# KVR_LABS_-_AEV_ENCODER_1_01-STM32.net
KiCad netlist of a schematic drawn in EAGLE
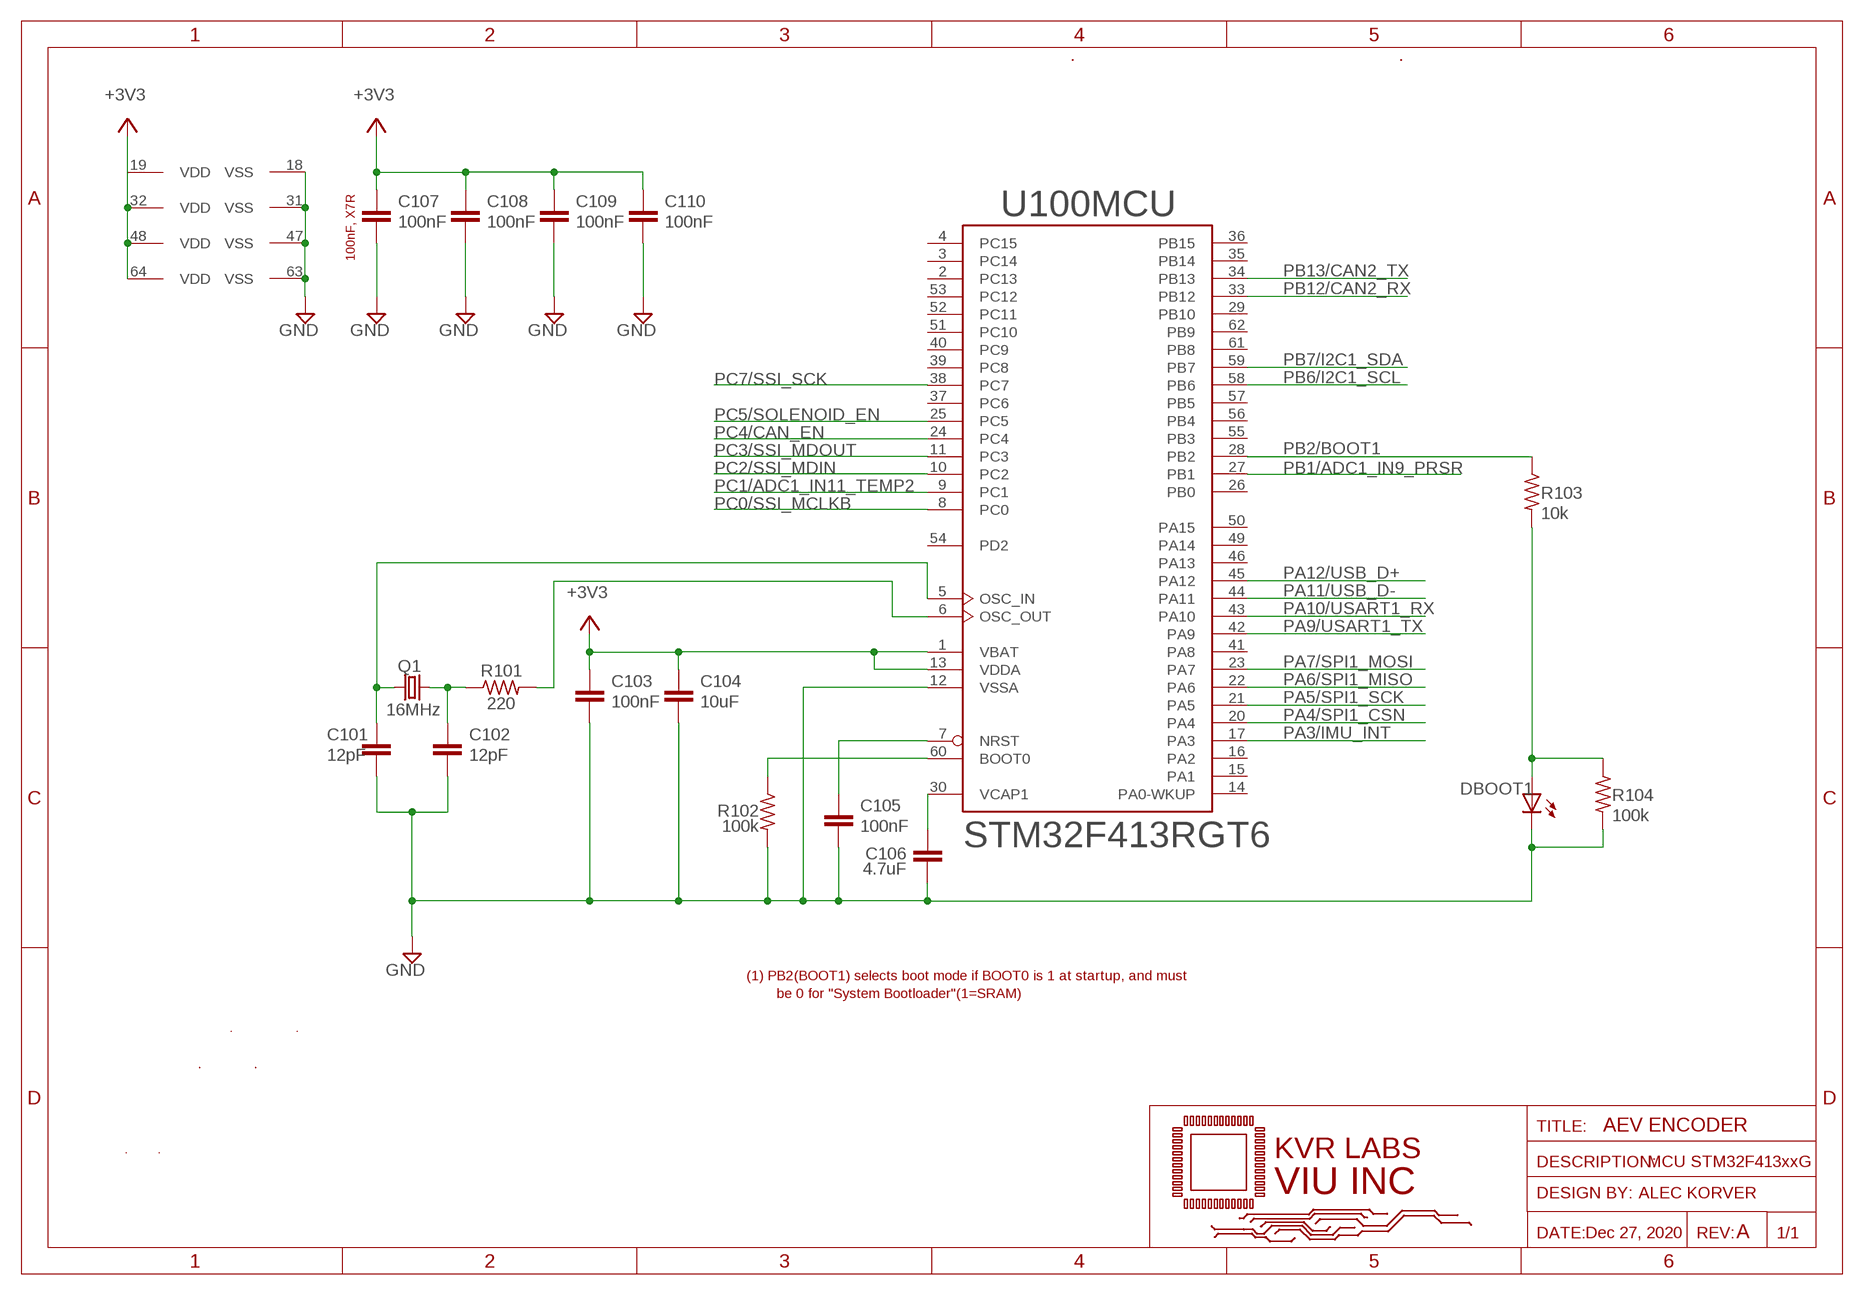
[diagram p0: schematic, sheet 1]
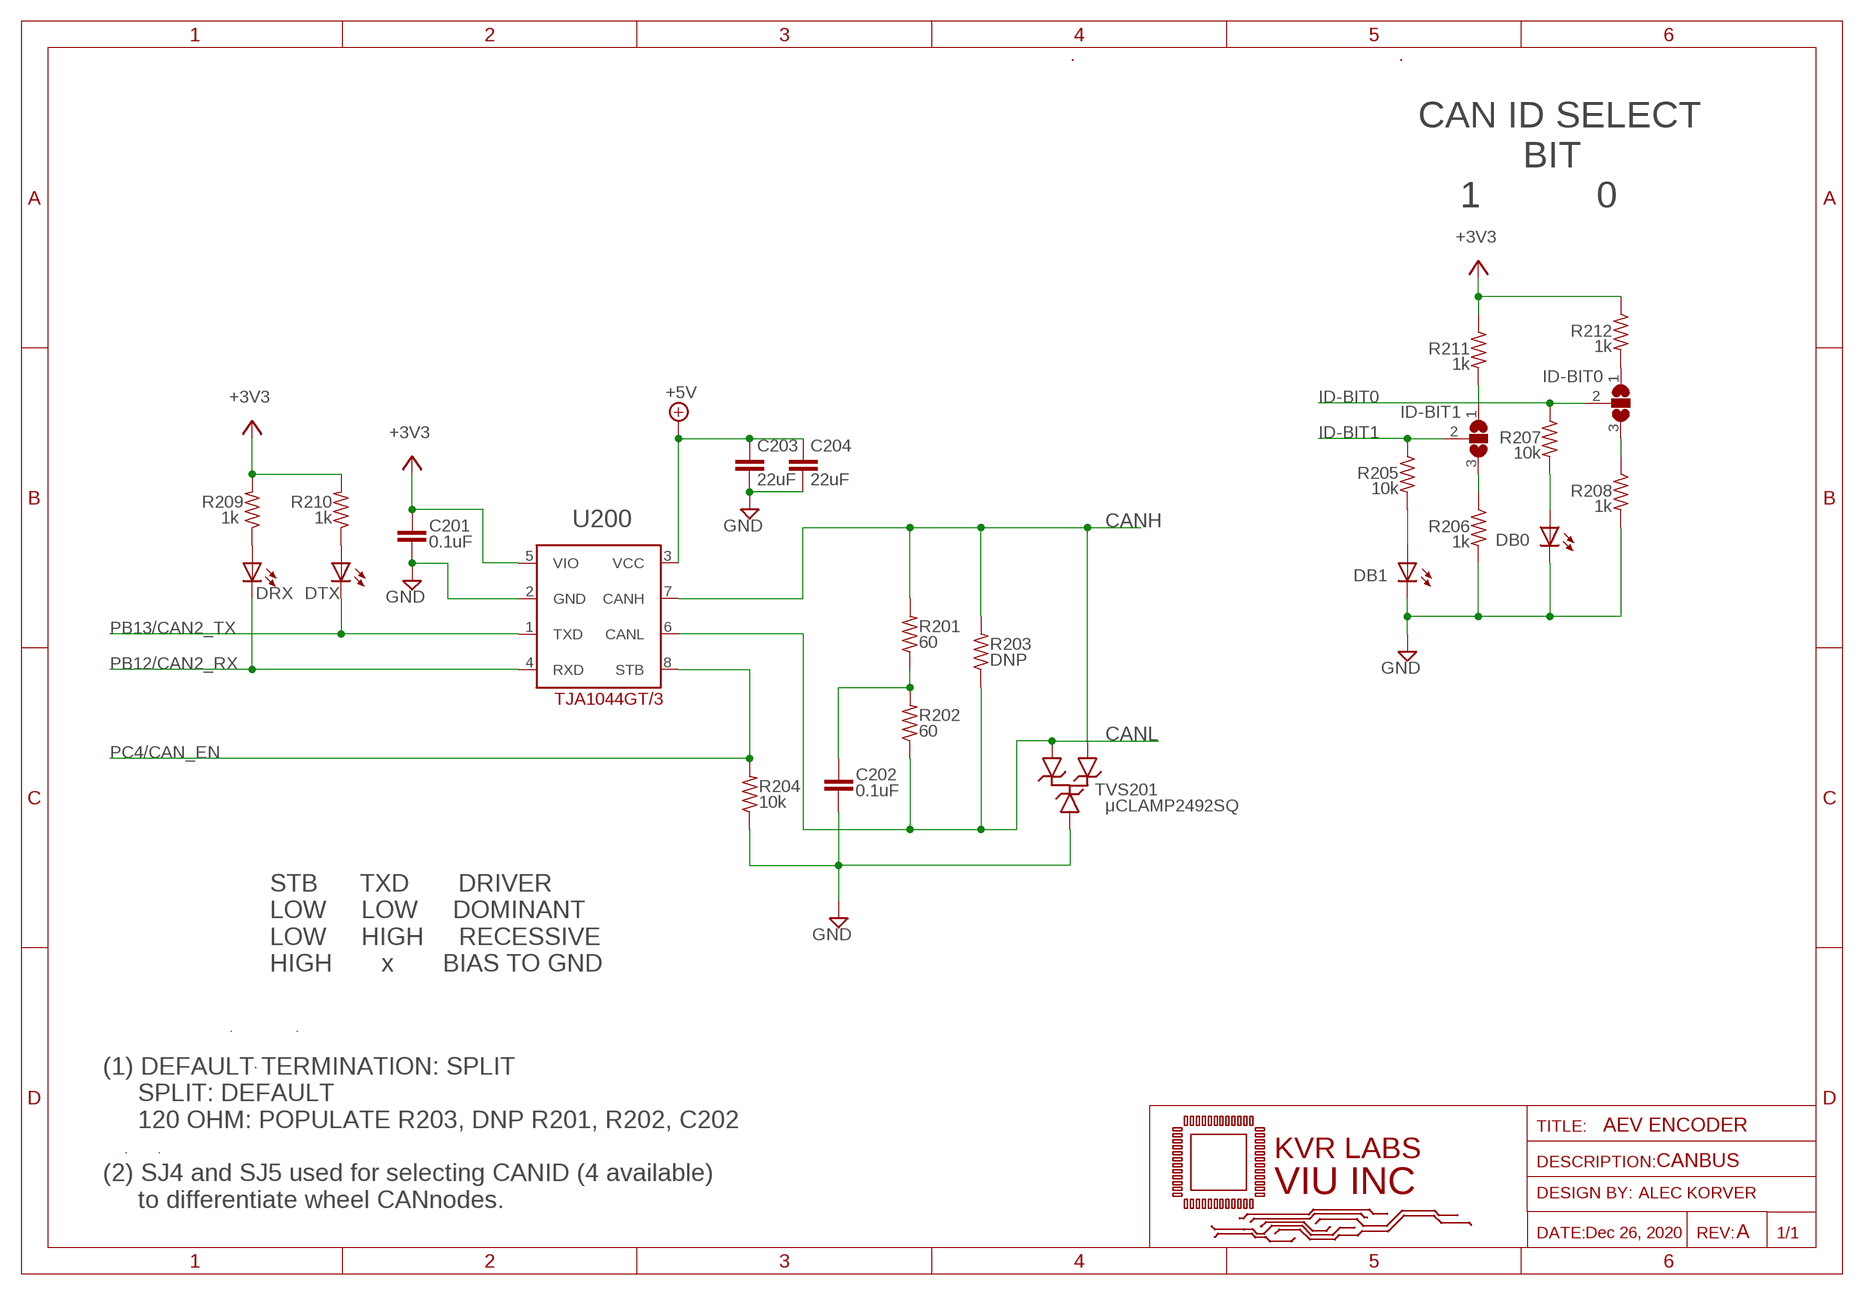
[diagram p1: schematic, sheet 2]
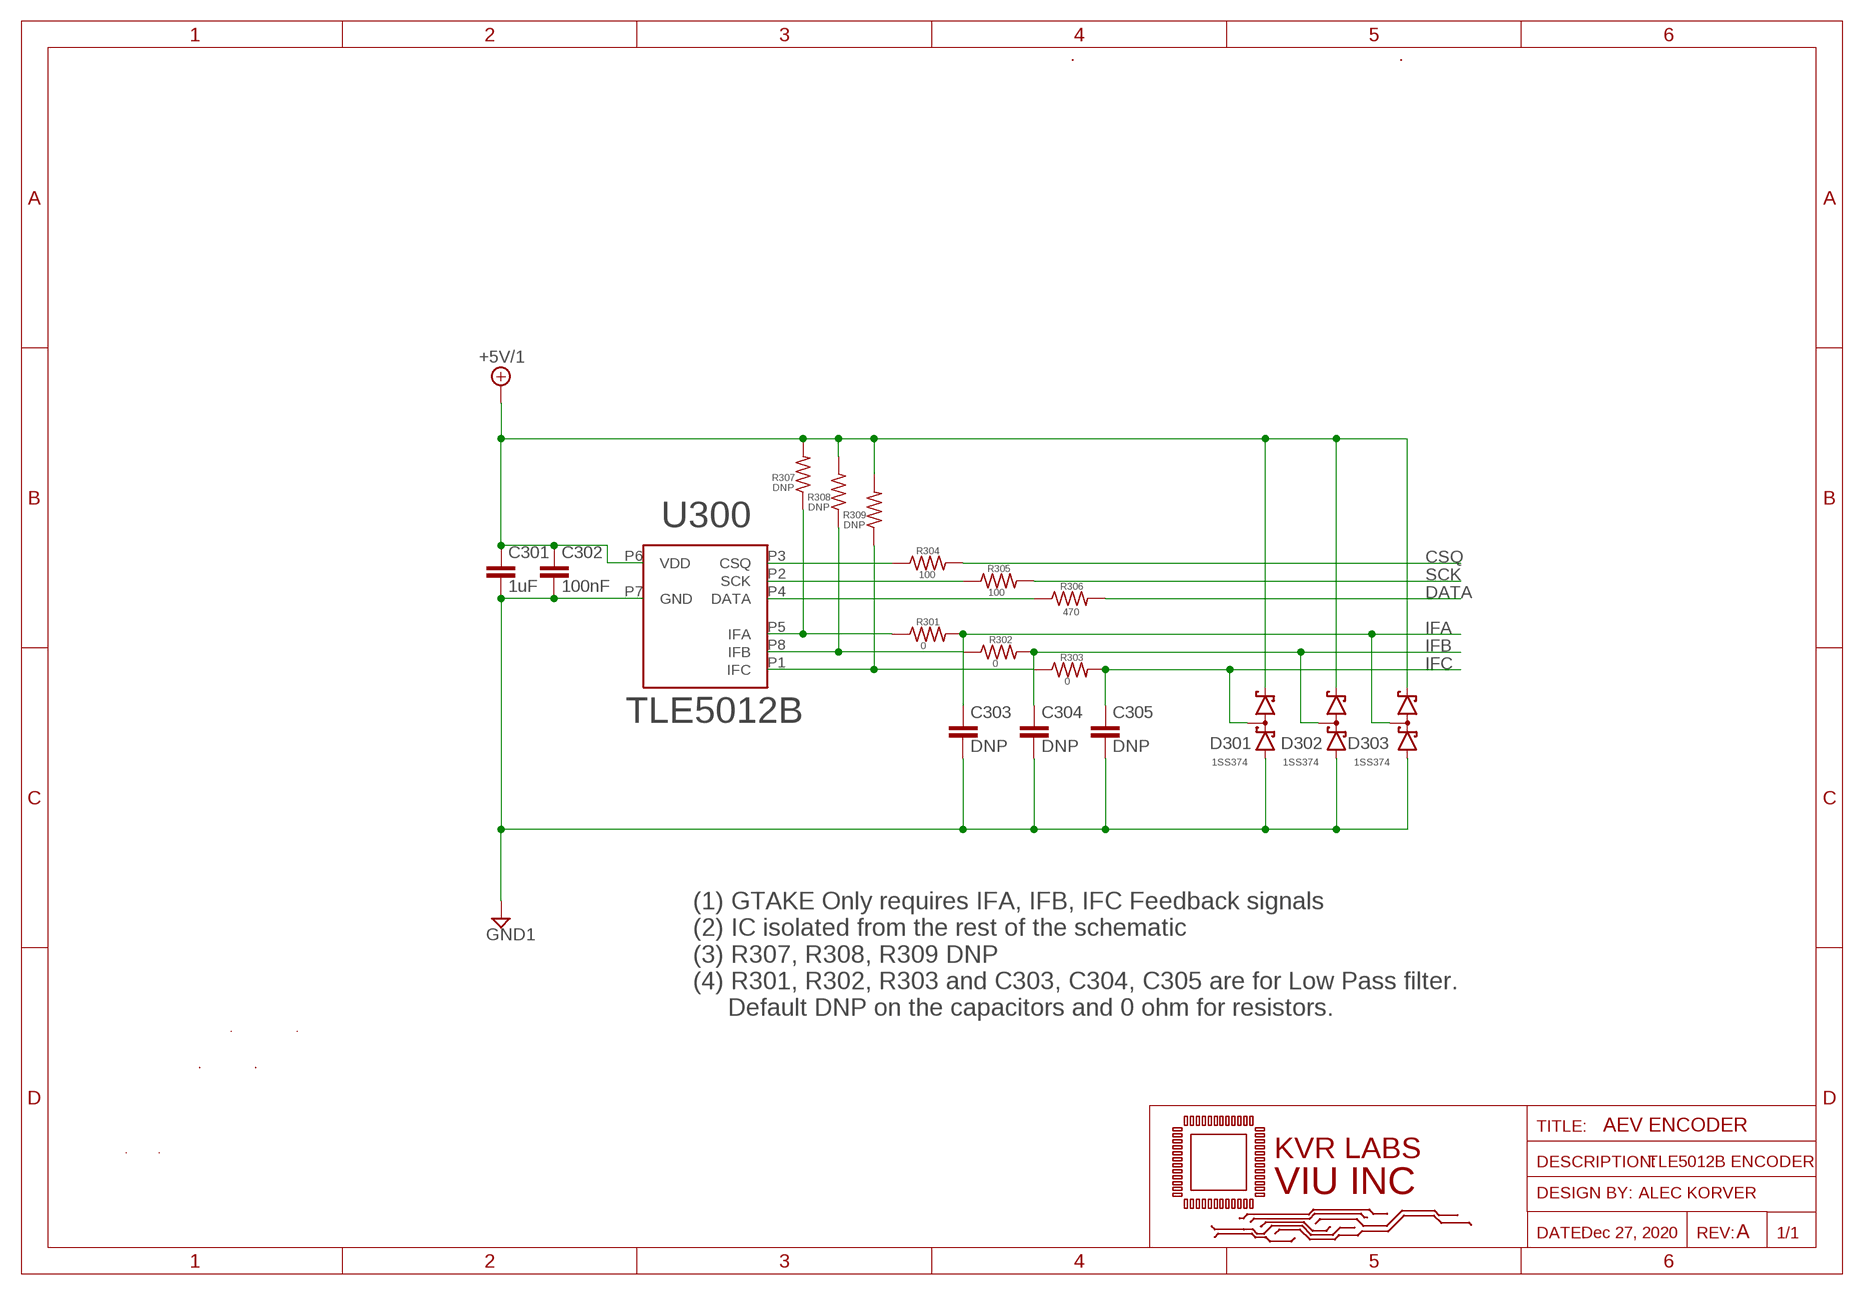
[diagram p2: schematic, sheet 3]
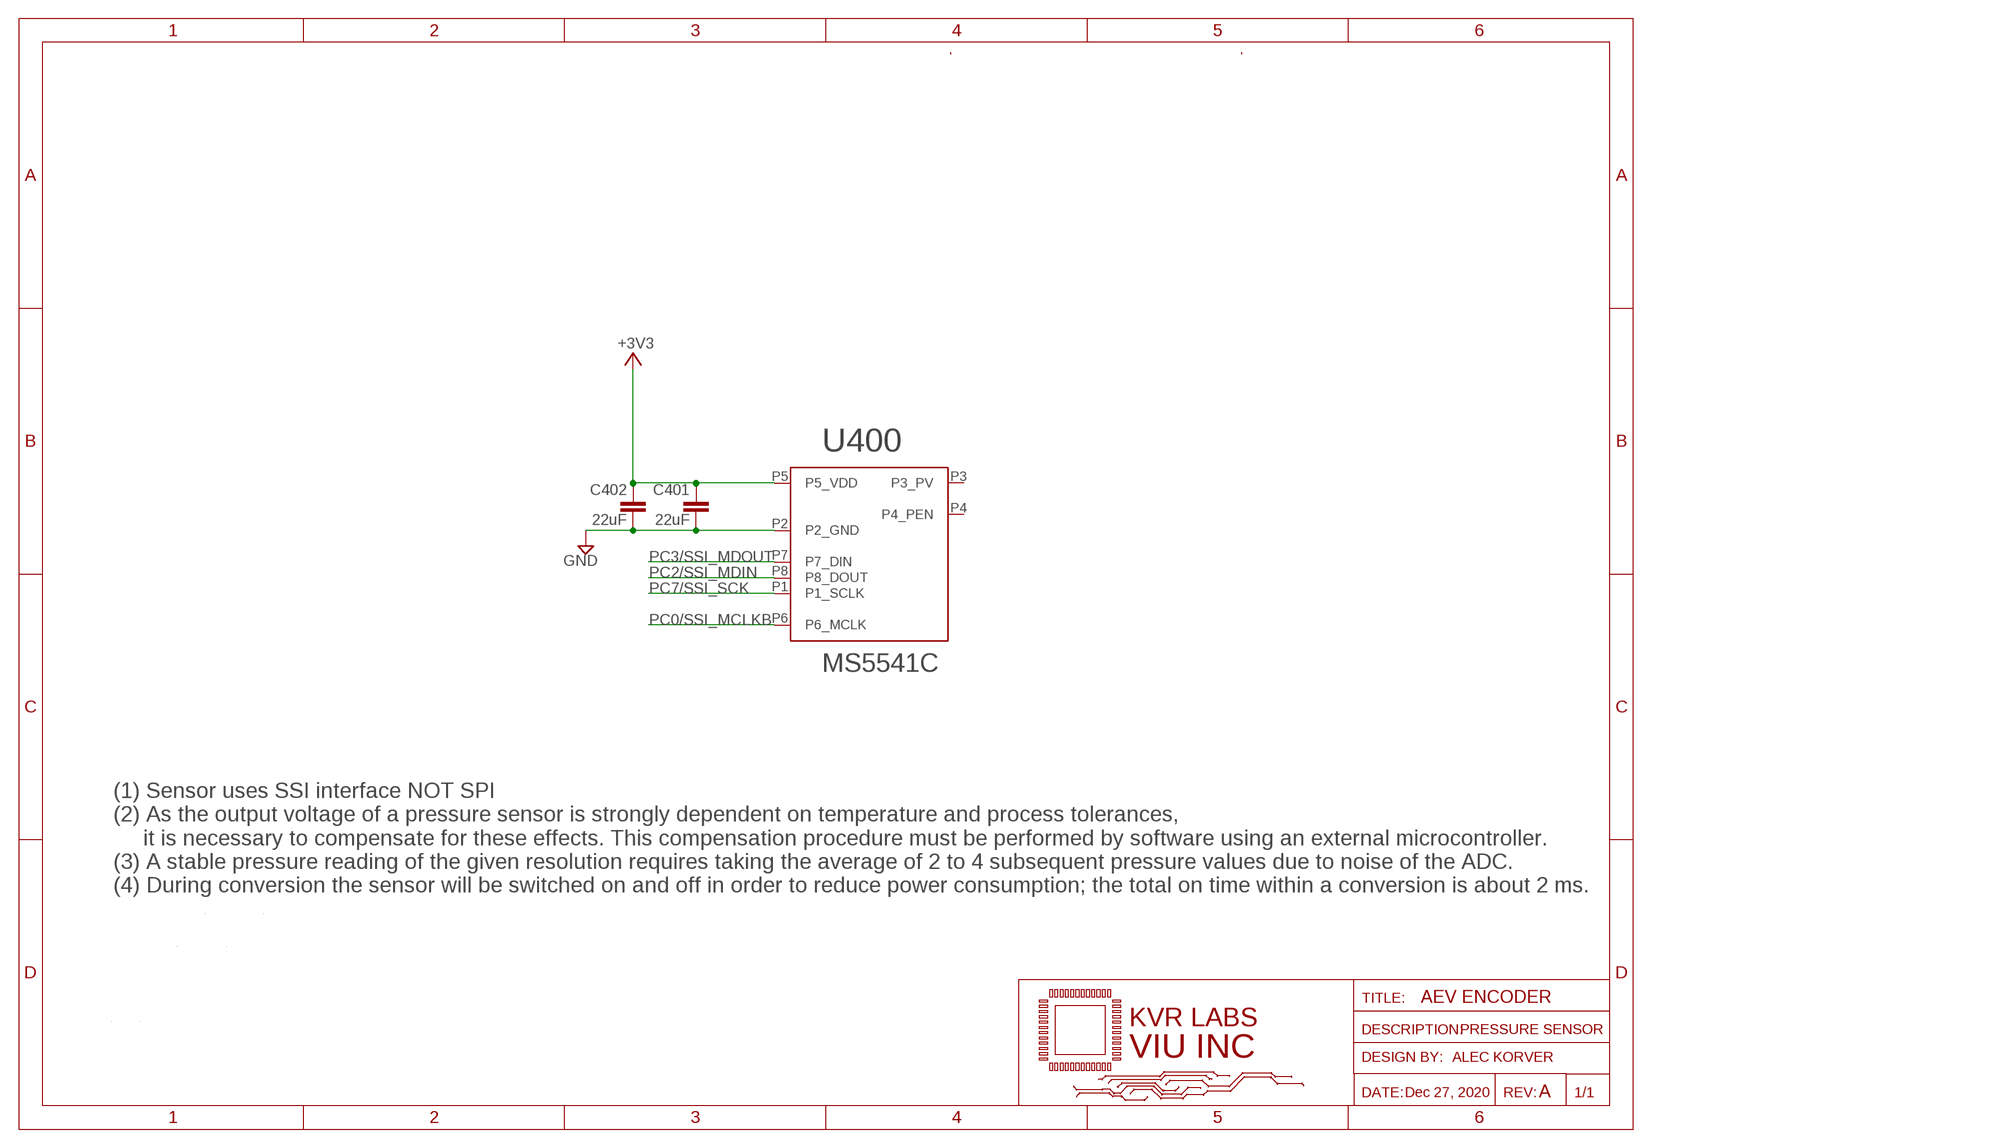
[diagram p3: schematic, sheet 4]
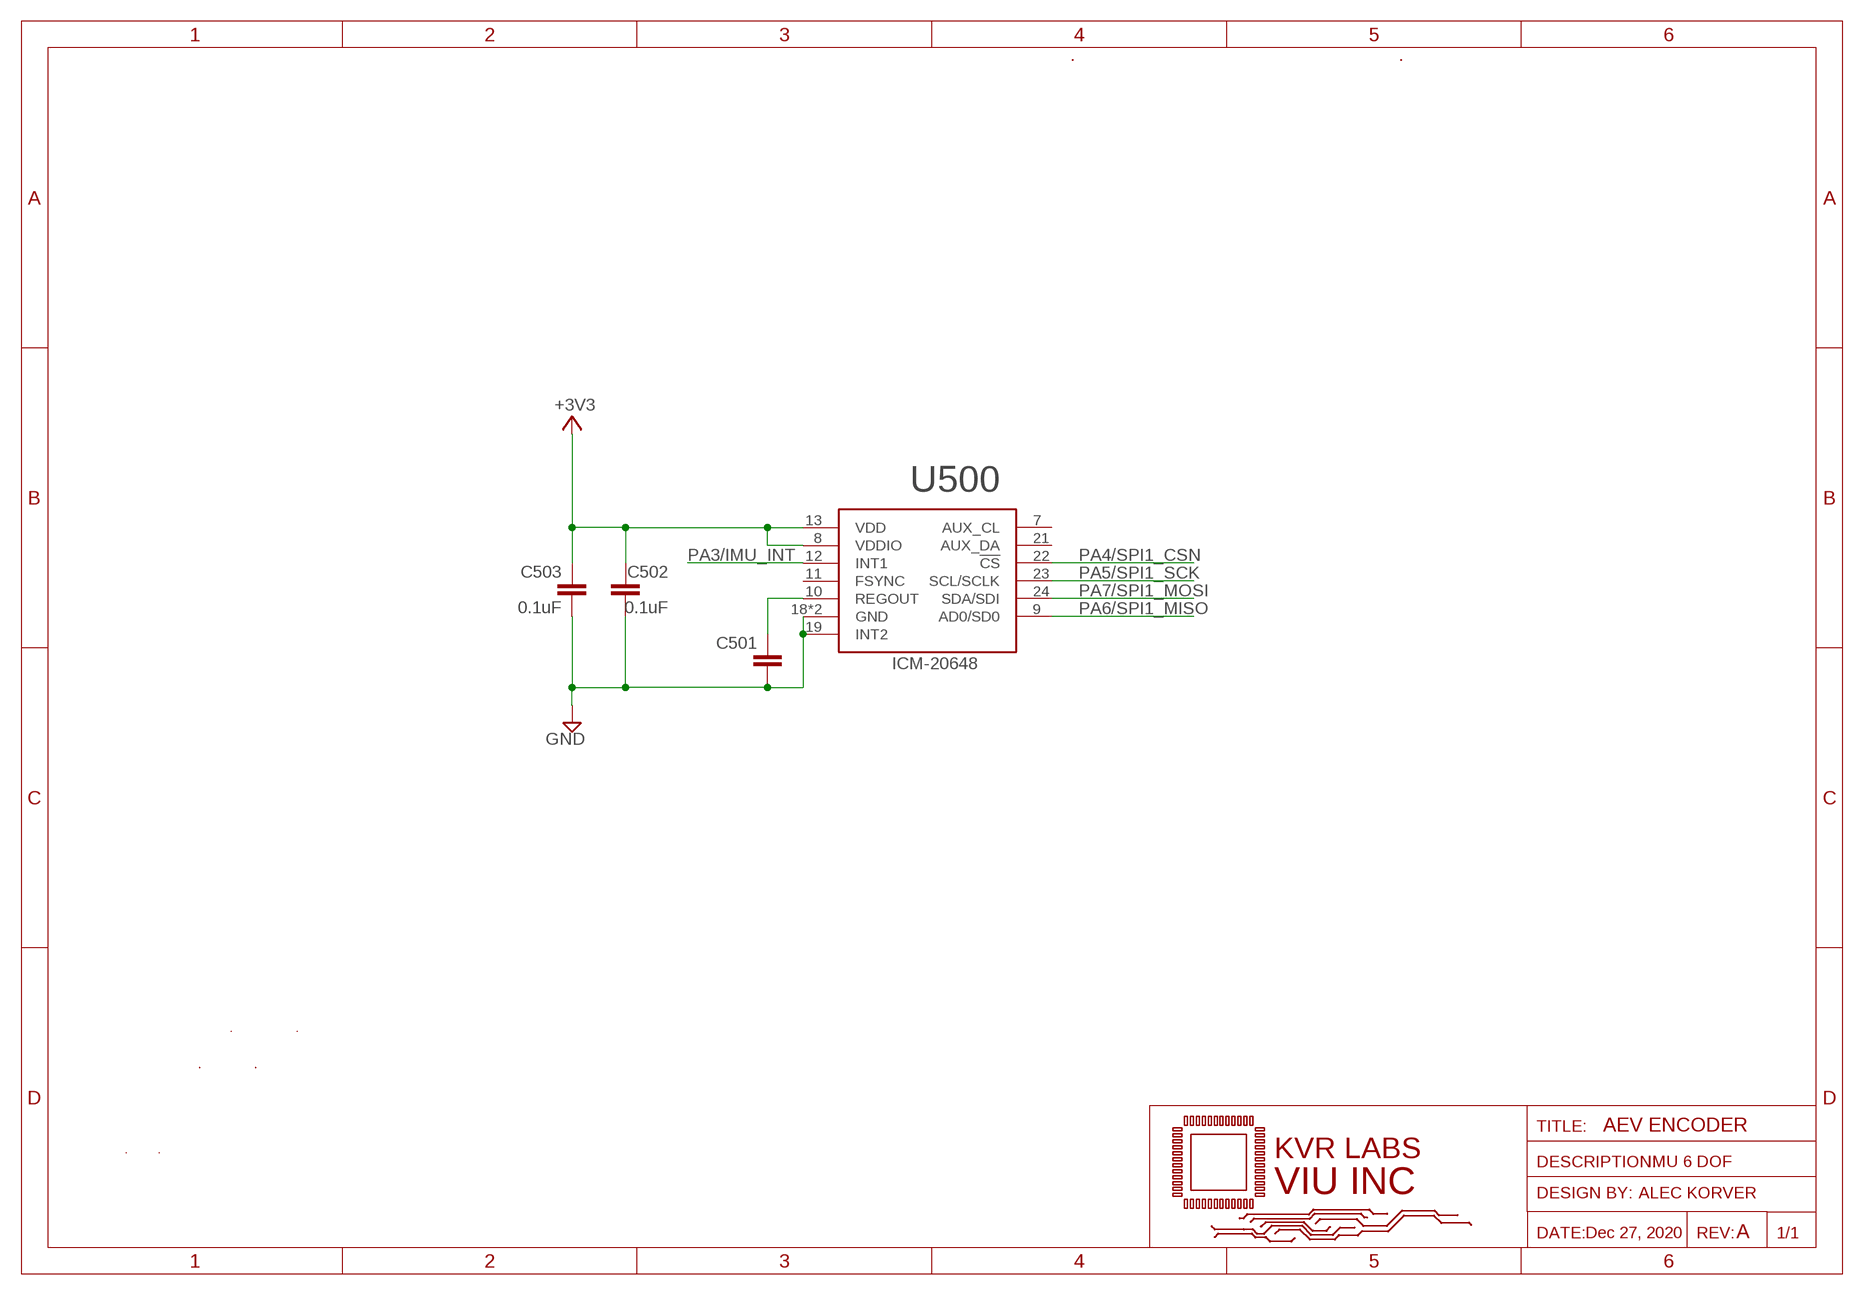
[diagram p4: schematic, sheet 5]
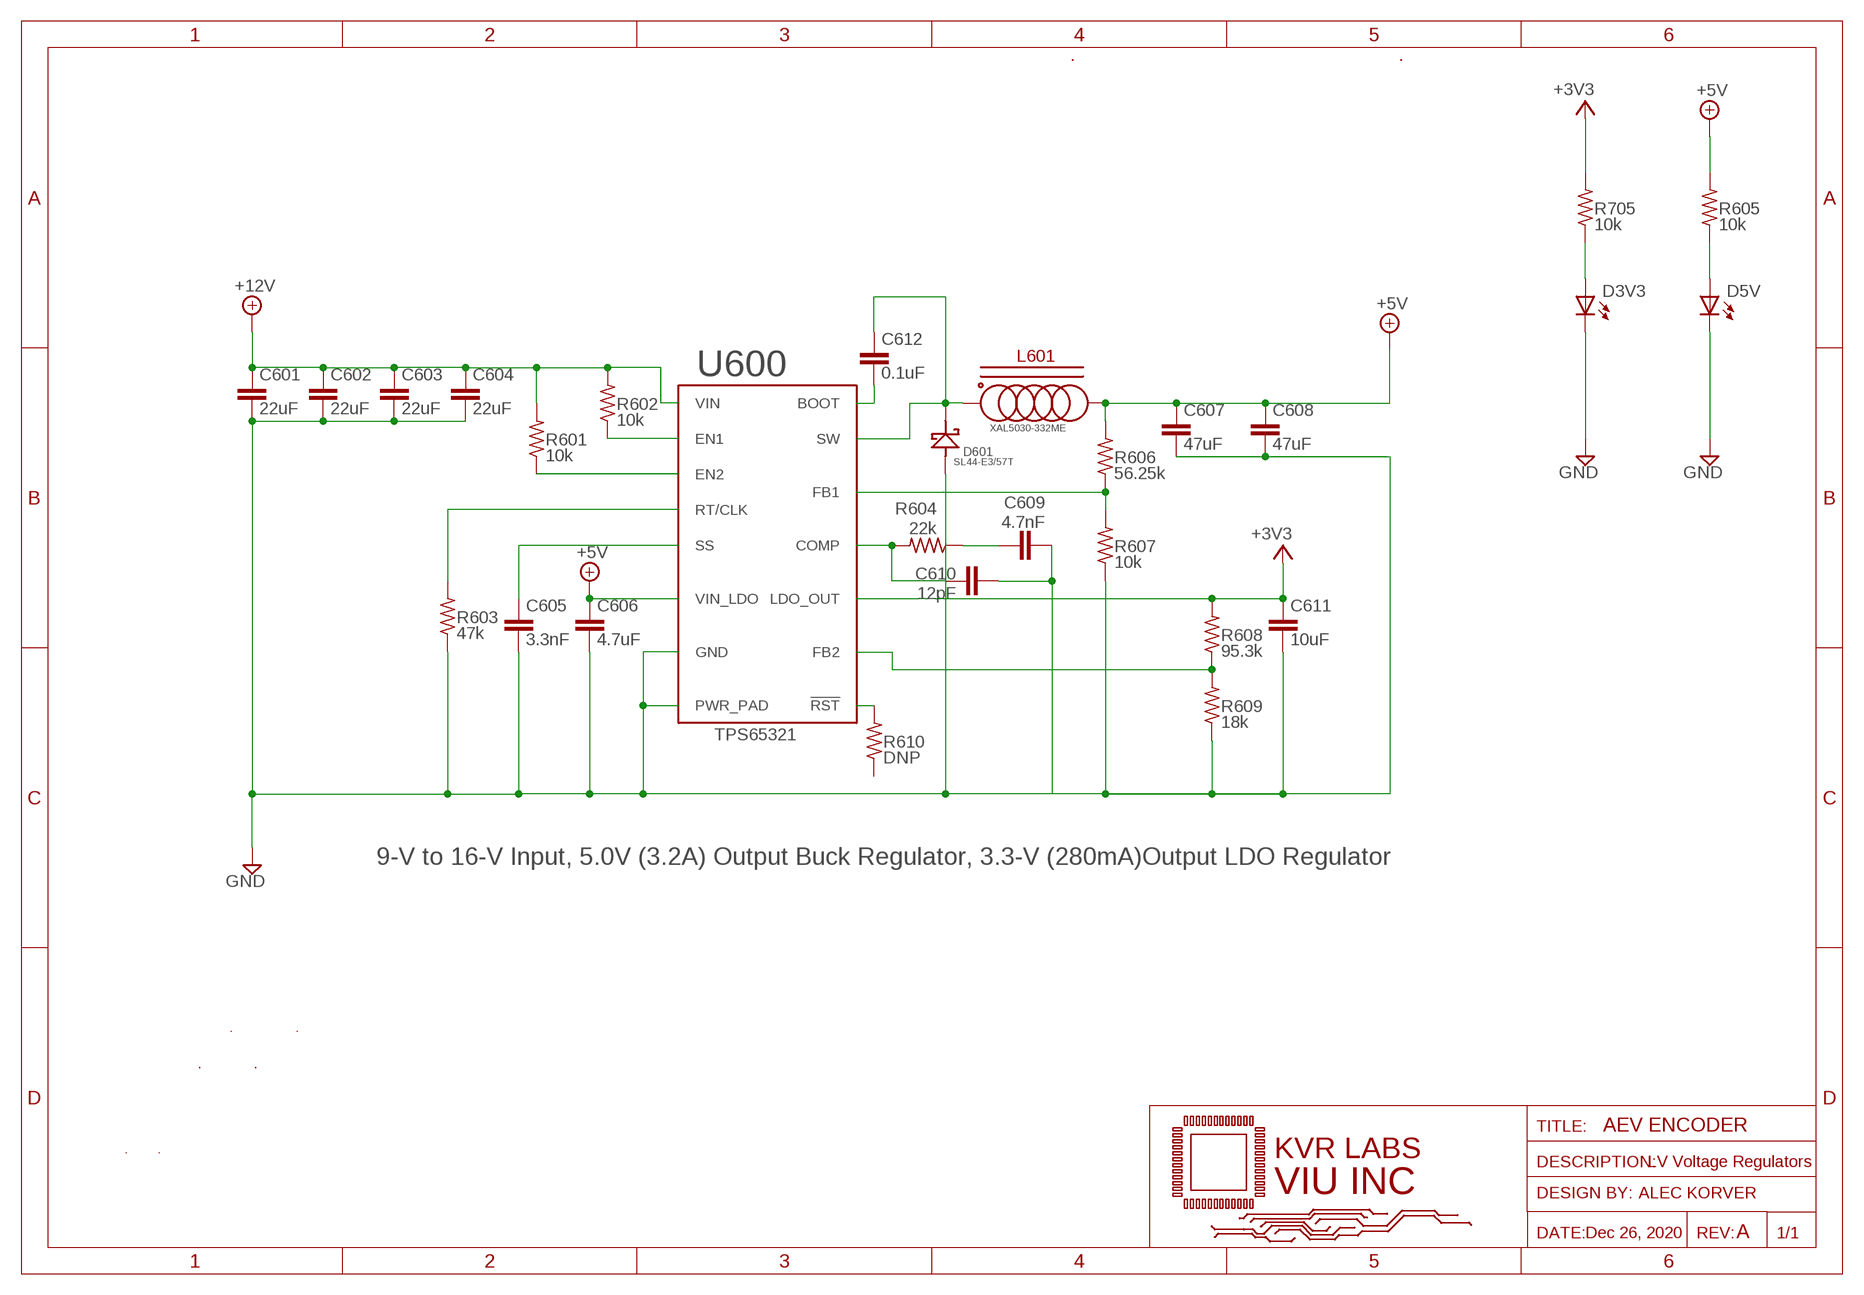
[diagram p5: schematic, sheet 6]
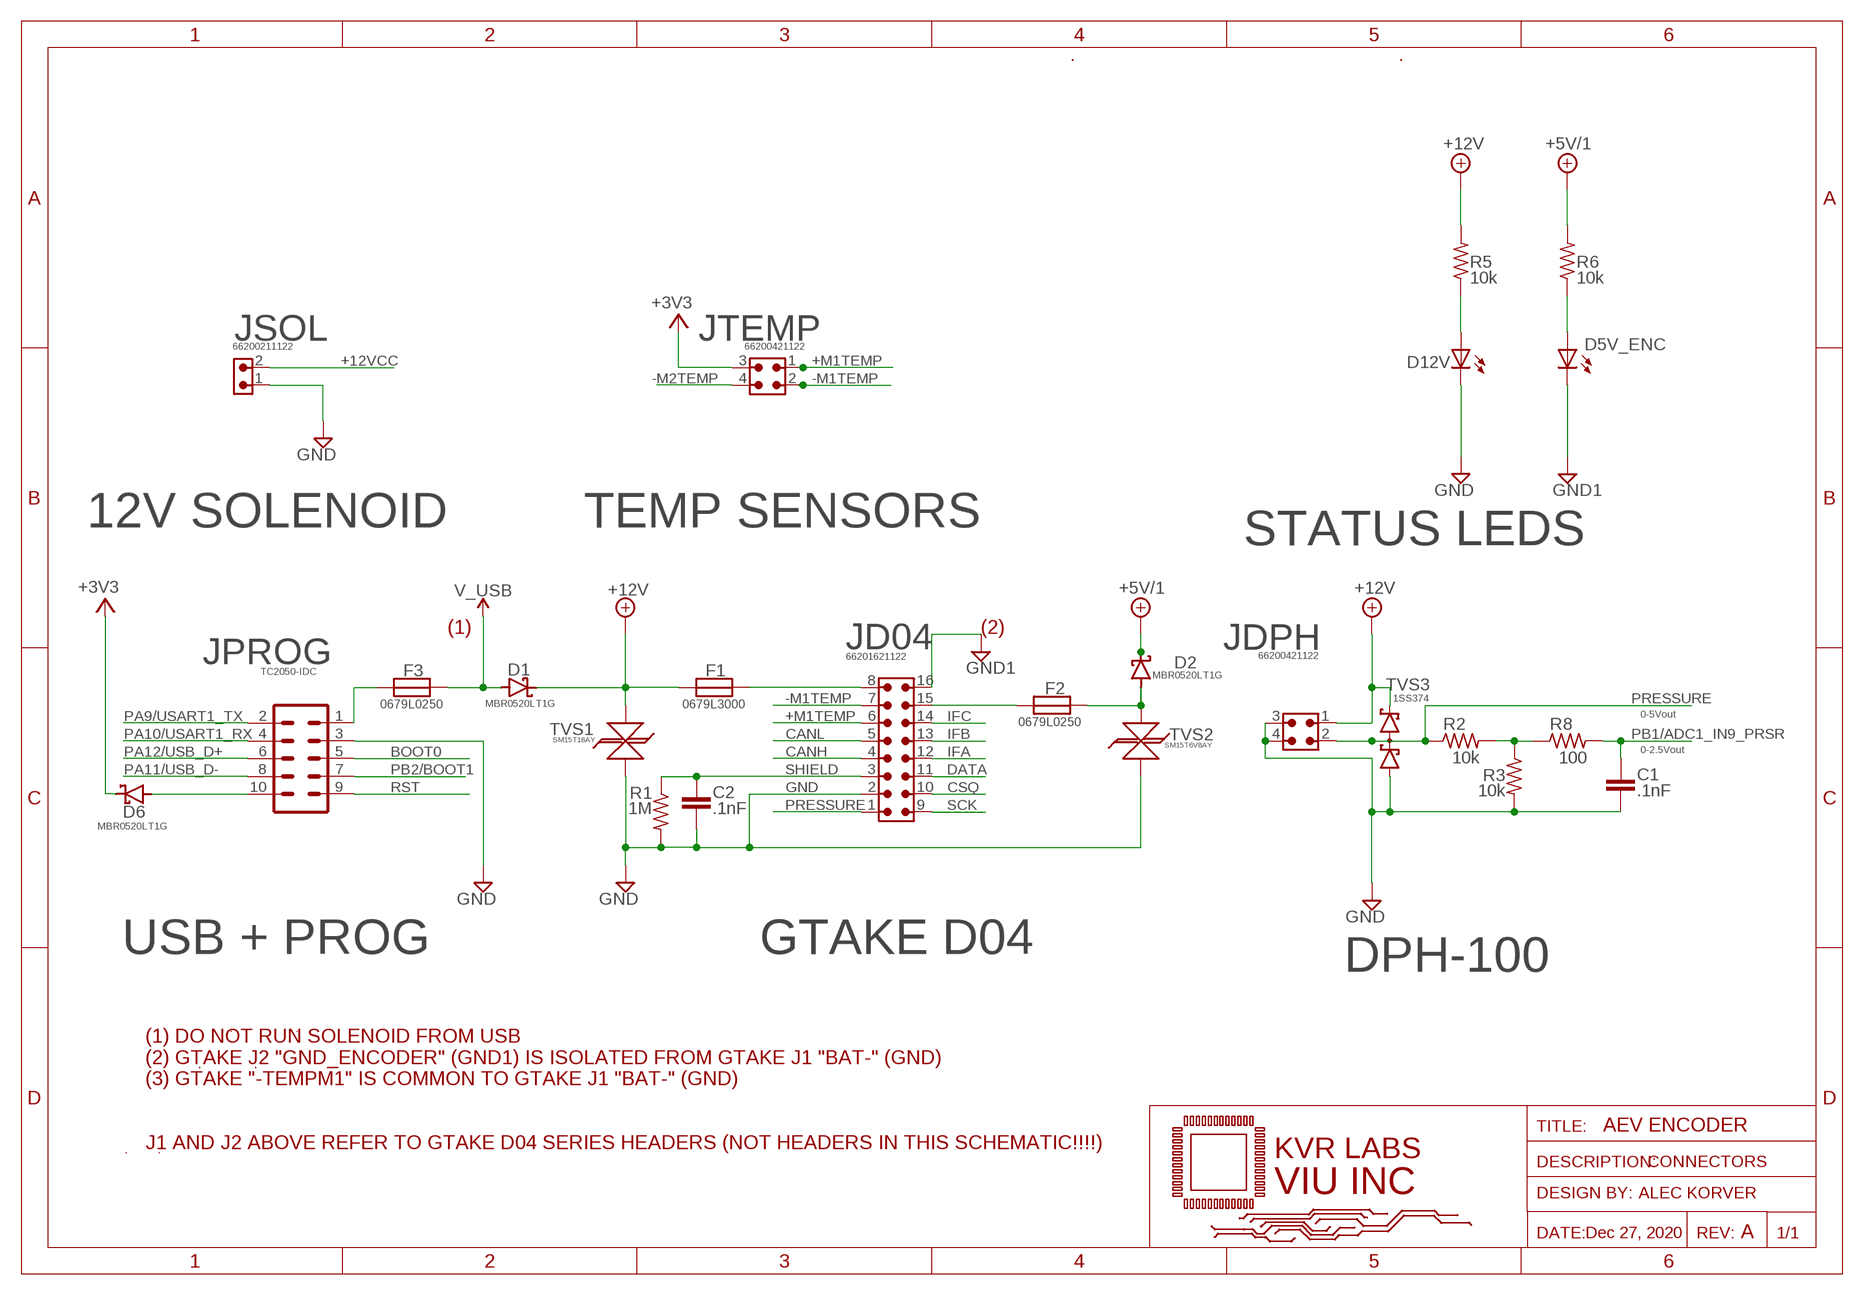
[diagram p6: schematic, sheet 7]
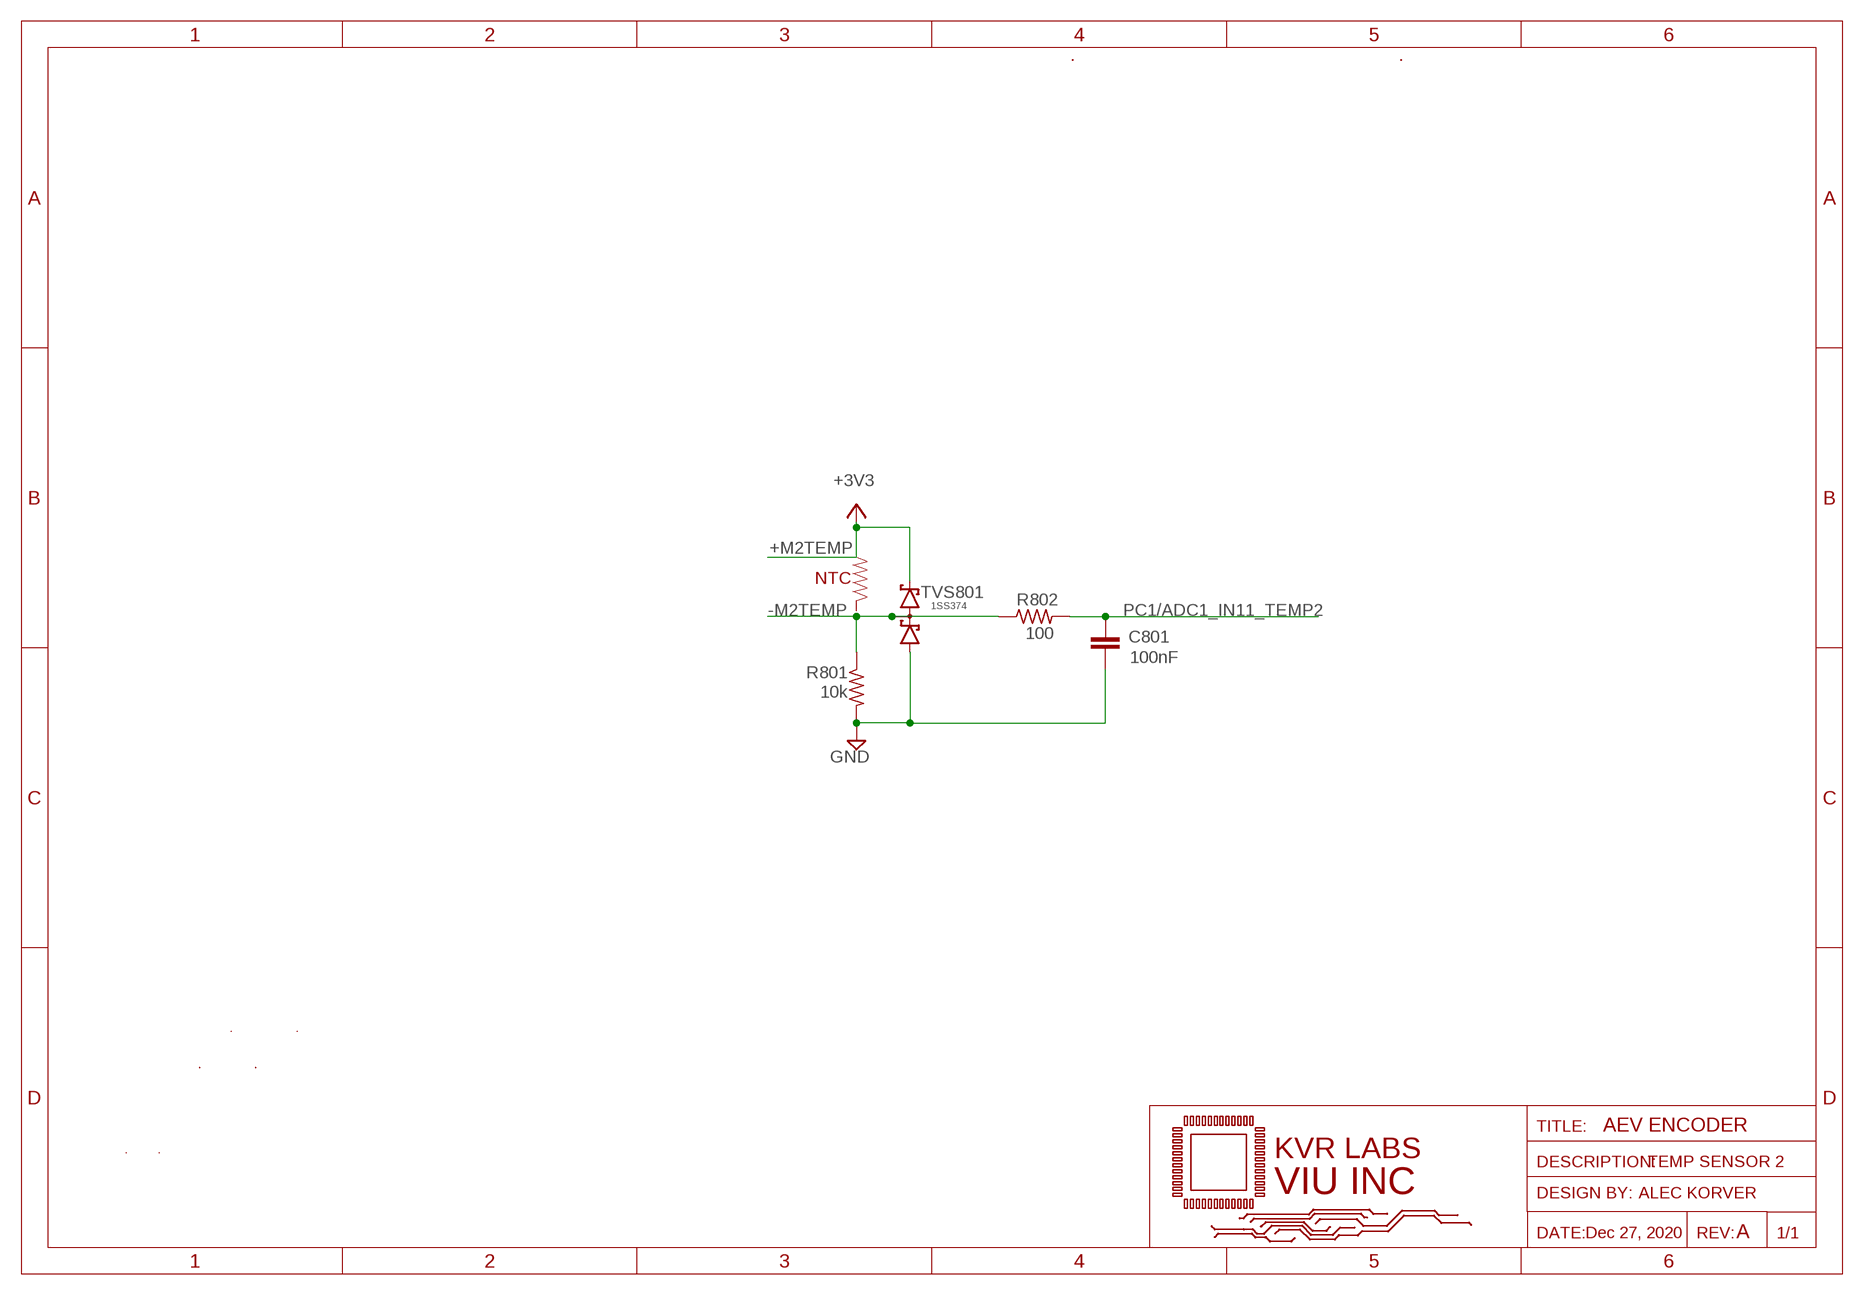
[diagram p7: schematic, sheet 8]
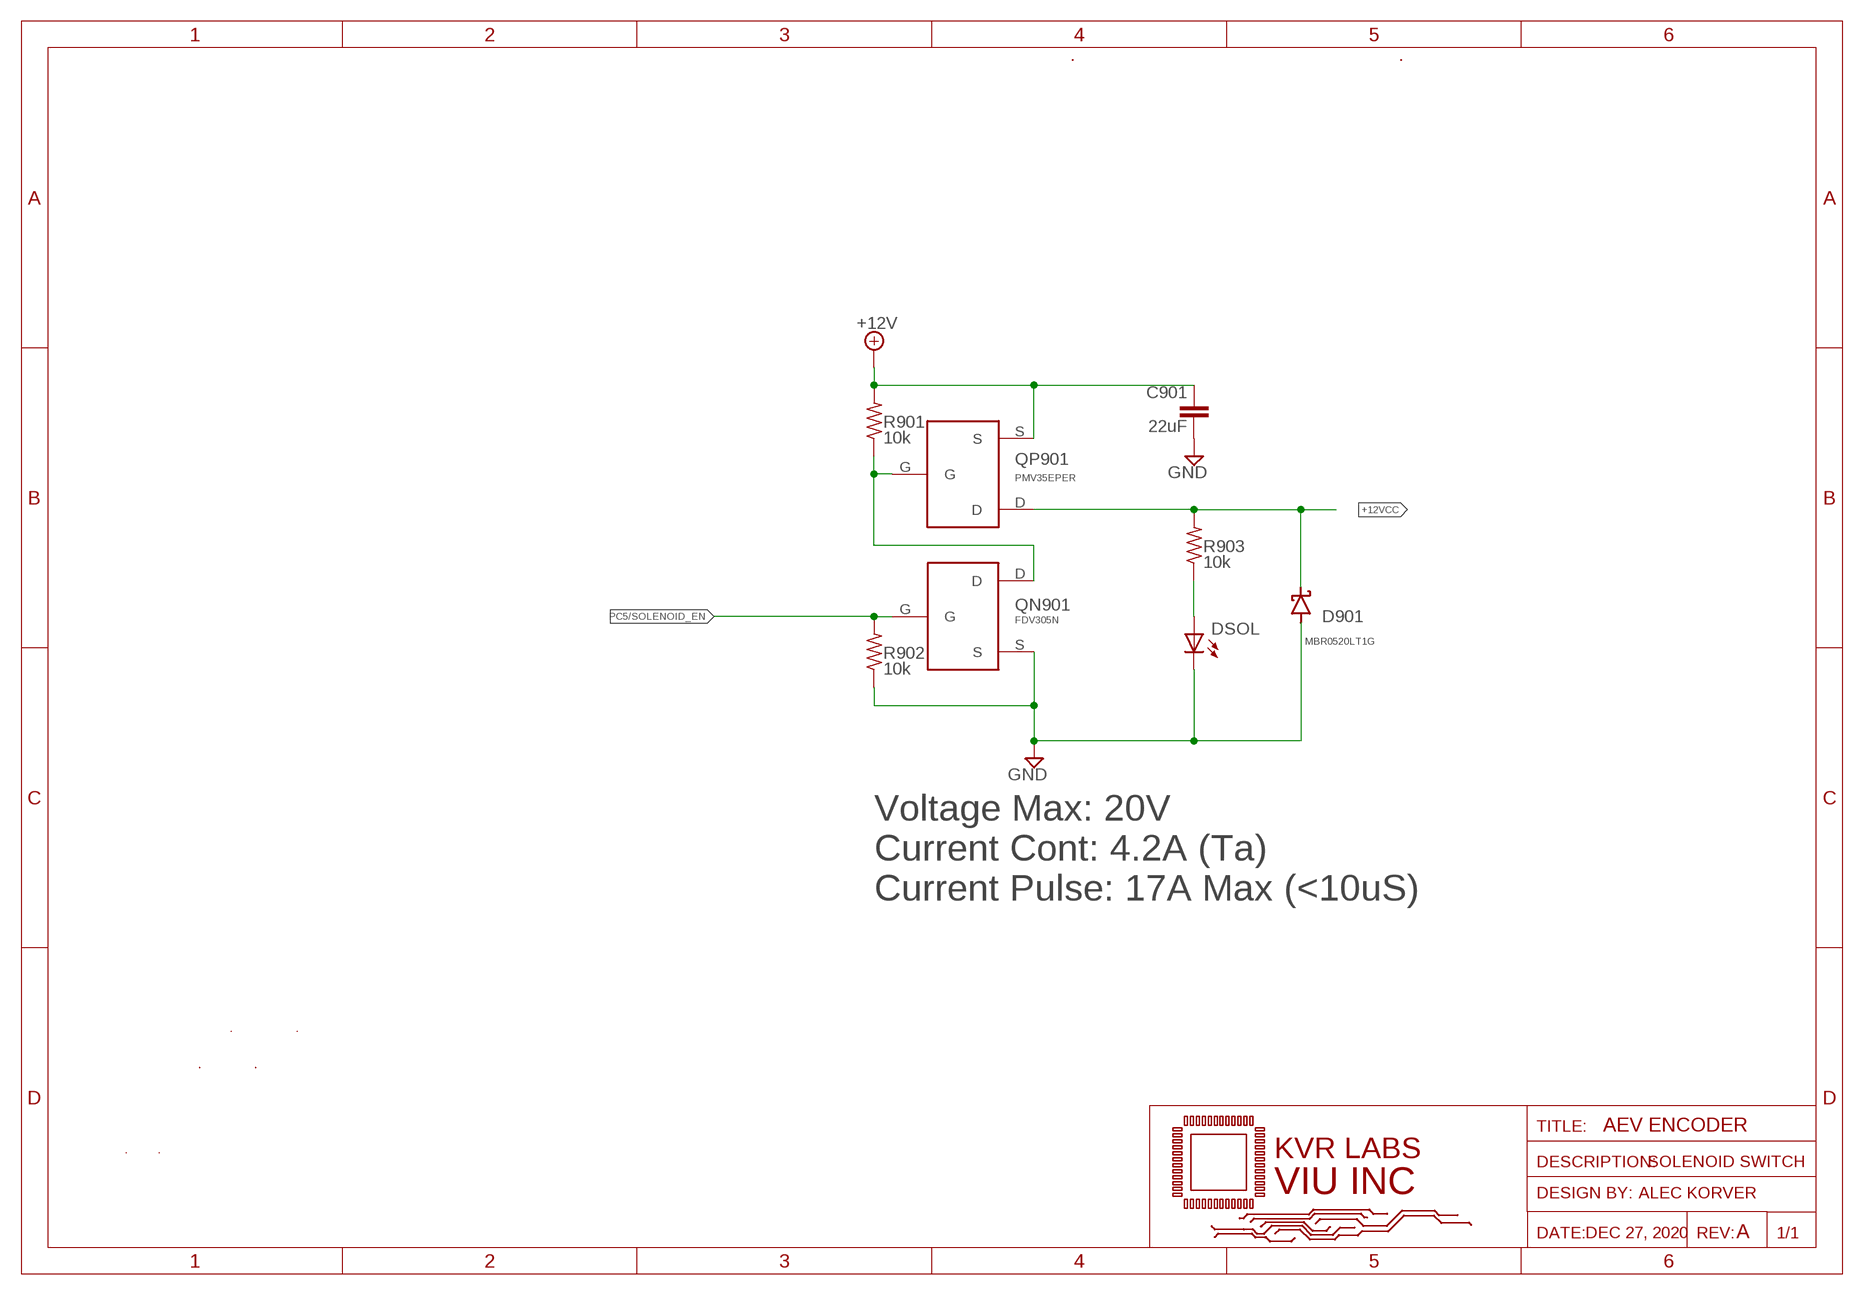
[diagram p8: schematic, sheet 9]

(export (version "E")
  (design (tool "Eeschema 10.0.6"))
  (components
    (comp (ref "C401")
      (value "22uF")
      (footprint "eagle-import:C1206")
      (libsource (lib "eagle-import") (part "rcl_334_C-EUC1206"))
    )
    (comp (ref "C402")
      (value "22uF")
      (footprint "eagle-import:C1206")
      (libsource (lib "eagle-import") (part "rcl_334_C-EUC1206"))
    )
    (comp (ref "U400")
      (value "MS5541C")
      (footprint "eagle-import:MS5541C")
      (libsource (lib "eagle-import") (part "MS5541C"))
    )
    (comp (ref "C101")
      (value "12pF")
      (footprint "eagle-import:C0603")
      (libsource (lib "eagle-import") (part "rcl_334_C-EUC0603"))
    )
    (comp (ref "C102")
      (value "12pF")
      (footprint "eagle-import:C0603")
      (libsource (lib "eagle-import") (part "rcl_334_C-EUC0603"))
    )
    (comp (ref "C103")
      (value "100nF")
      (footprint "eagle-import:C0603")
      (libsource (lib "eagle-import") (part "rcl_334_C-EUC0603"))
    )
    (comp (ref "C104")
      (value "10uF")
      (footprint "eagle-import:C0603")
      (libsource (lib "eagle-import") (part "rcl_334_C-EUC0603"))
    )
    (comp (ref "C105")
      (value "100nF")
      (footprint "eagle-import:C0603")
      (libsource (lib "eagle-import") (part "rcl_334_C-EUC0603"))
    )
    (comp (ref "C106")
      (value "4.7uF")
      (footprint "eagle-import:C0603")
      (libsource (lib "eagle-import") (part "rcl_334_C-EUC0603"))
    )
    (comp (ref "C107")
      (value "100nF")
      (footprint "eagle-import:C0603")
      (libsource (lib "eagle-import") (part "rcl_334_C-EUC0603"))
    )
    (comp (ref "C108")
      (value "100nF")
      (footprint "eagle-import:C0603")
      (libsource (lib "eagle-import") (part "rcl_334_C-EUC0603"))
    )
    (comp (ref "C109")
      (value "100nF")
      (footprint "eagle-import:C0603")
      (libsource (lib "eagle-import") (part "rcl_334_C-EUC0603"))
    )
    (comp (ref "C110")
      (value "100nF")
      (footprint "eagle-import:C0603")
      (libsource (lib "eagle-import") (part "rcl_334_C-EUC0603"))
    )
    (comp (ref "DBOOT1")
      (value "LEDCHIPLED_0805")
      (footprint "eagle-import:CHIPLED_0805")
      (libsource (lib "eagle-import") (part "LEDCHIPLED_0805"))
    )
    (comp (ref "Q1")
      (value "16MHz")
      (footprint "eagle-import:CRY3225-4")
      (libsource (lib "eagle-import") (part "CRYTALS32"))
    )
    (comp (ref "R101")
      (value "220")
      (footprint "eagle-import:R0603")
      (libsource (lib "eagle-import") (part "R-US_R0603"))
    )
    (comp (ref "R102")
      (value "100k")
      (footprint "eagle-import:R0603")
      (libsource (lib "eagle-import") (part "R-US_R0603"))
    )
    (comp (ref "R103")
      (value "10k")
      (footprint "eagle-import:R0603")
      (libsource (lib "eagle-import") (part "R-US_R0603"))
    )
    (comp (ref "R104")
      (value "100k")
      (footprint "eagle-import:R0603")
      (libsource (lib "eagle-import") (part "R-US_R0603"))
    )
    (comp (ref "U100")
      (value "STM32F413RGT6")
      (footprint "eagle-import:LQFP64_STMLIB")
      (fields (field (name "MXCODE") "STM32F413RGT6"))
      (libsource (lib "eagle-import") (part "STM32F401RTB"))
    )
    (comp (ref "C501")
      (value "0.1uF")
      (footprint "eagle-import:C0603")
      (libsource (lib "eagle-import") (part "rcl_334_C-EUC0603"))
    )
    (comp (ref "C502")
      (value "0.1uF")
      (footprint "eagle-import:C0603")
      (libsource (lib "eagle-import") (part "rcl_334_C-EUC0603"))
    )
    (comp (ref "C503")
      (value "0.1uF")
      (footprint "eagle-import:C0603")
      (libsource (lib "eagle-import") (part "rcl_334_C-EUC0603"))
    )
    (comp (ref "U500")
      (value "ICM-20648")
      (footprint "eagle-import:ICM-20648")
      (libsource (lib "eagle-import") (part "ICM-20648"))
    )
    (comp (ref "C201")
      (value "0.1uF")
      (footprint "eagle-import:C0603")
      (libsource (lib "eagle-import") (part "rcl_23965951_C-EUC0603"))
    )
    (comp (ref "C202")
      (value "0.1uF")
      (footprint "eagle-import:C0603")
      (libsource (lib "eagle-import") (part "rcl_23965951_C-EUC0603"))
    )
    (comp (ref "C203")
      (value "22uF")
      (footprint "eagle-import:C1206")
      (libsource (lib "eagle-import") (part "rcl_334_C-EUC1206"))
    )
    (comp (ref "C204")
      (value "22uF")
      (footprint "eagle-import:C1206")
      (libsource (lib "eagle-import") (part "rcl_334_C-EUC1206"))
    )
    (comp (ref "D201")
      (value "μCLAMP2492SQ")
      (footprint "eagle-import:SOT-23_3L_ONS")
      (fields (field (name "MODEL") "μCLAMP2492SQ"))
      (libsource (lib "eagle-import") (part "μCLAMP2492SQ"))
    )
    (comp (ref "DB0")
      (value "LEDCHIPLED_0805")
      (footprint "eagle-import:CHIPLED_0805")
      (libsource (lib "eagle-import") (part "LEDCHIPLED_0805"))
    )
    (comp (ref "DB1")
      (value "LEDCHIPLED_0805")
      (footprint "eagle-import:CHIPLED_0805")
      (libsource (lib "eagle-import") (part "LEDCHIPLED_0805"))
    )
    (comp (ref "DRX")
      (value "LEDCHIPLED_0805")
      (footprint "eagle-import:CHIPLED_0805")
      (libsource (lib "eagle-import") (part "LEDCHIPLED_0805"))
    )
    (comp (ref "DTX")
      (value "LEDCHIPLED_0805")
      (footprint "eagle-import:CHIPLED_0805")
      (libsource (lib "eagle-import") (part "LEDCHIPLED_0805"))
    )
    (comp (ref "ID-BIT0")
      (value "SJ2W")
      (footprint "eagle-import:SJ_2")
      (libsource (lib "eagle-import") (part "SJ2W"))
    )
    (comp (ref "ID-BIT1")
      (value "SJ2W")
      (footprint "eagle-import:SJ_2")
      (libsource (lib "eagle-import") (part "SJ2W"))
    )
    (comp (ref "R201")
      (value "60")
      (footprint "eagle-import:R0603")
      (libsource (lib "eagle-import") (part "R-US_R0603"))
    )
    (comp (ref "R202")
      (value "60")
      (footprint "eagle-import:R0603")
      (libsource (lib "eagle-import") (part "R-US_R0603"))
    )
    (comp (ref "R203")
      (value "DNP")
      (footprint "eagle-import:R0603")
      (libsource (lib "eagle-import") (part "R-US_R0603"))
    )
    (comp (ref "R204")
      (value "10k")
      (footprint "eagle-import:R0603")
      (libsource (lib "eagle-import") (part "R-US_R0603"))
    )
    (comp (ref "R205")
      (value "10k")
      (footprint "eagle-import:R0603")
      (libsource (lib "eagle-import") (part "R-US_R0603"))
    )
    (comp (ref "R206")
      (value "1k")
      (footprint "eagle-import:R0603")
      (libsource (lib "eagle-import") (part "R-US_R0603"))
    )
    (comp (ref "R207")
      (value "10k")
      (footprint "eagle-import:R0603")
      (libsource (lib "eagle-import") (part "R-US_R0603"))
    )
    (comp (ref "R208")
      (value "1k")
      (footprint "eagle-import:R0603")
      (libsource (lib "eagle-import") (part "R-US_R0603"))
    )
    (comp (ref "R209")
      (value "1k")
      (footprint "eagle-import:R0603")
      (libsource (lib "eagle-import") (part "R-US_R0603"))
    )
    (comp (ref "R210")
      (value "1k")
      (footprint "eagle-import:R0603")
      (libsource (lib "eagle-import") (part "R-US_R0603"))
    )
    (comp (ref "R211")
      (value "1k")
      (footprint "eagle-import:R0603")
      (libsource (lib "eagle-import") (part "R-US_R0603"))
    )
    (comp (ref "R212")
      (value "1k")
      (footprint "eagle-import:R0603")
      (libsource (lib "eagle-import") (part "R-US_R0603"))
    )
    (comp (ref "U200")
      (value "TJA1044GT/3")
      (footprint "eagle-import:SO-8_S_LIT")
      (libsource (lib "eagle-import") (part "TJA1044GT/3"))
    )
    (comp (ref "C801")
      (value "100nF")
      (footprint "eagle-import:C0603")
      (libsource (lib "eagle-import") (part "C-EUC0603"))
    )
    (comp (ref "R801")
      (value "10k")
      (footprint "eagle-import:R0603")
      (libsource (lib "eagle-import") (part "rcl_334_R-US_R0603"))
    )
    (comp (ref "R802")
      (value "100")
      (footprint "eagle-import:R0603")
      (libsource (lib "eagle-import") (part "R-US_R0603"))
    )
    (comp (ref "TVS801")
      (value "BAS70-04")
      (footprint "eagle-import:SOT23")
      (fields (field (name "MODEL") "1SS374"))
      (libsource (lib "eagle-import") (part "BAS70-04"))
    )
    (comp (ref "C301")
      (value "1uF")
      (footprint "eagle-import:C0603")
      (libsource (lib "eagle-import") (part "rcl_334_C-EUC0603"))
    )
    (comp (ref "C302")
      (value "100nF")
      (footprint "eagle-import:C0603")
      (libsource (lib "eagle-import") (part "rcl_334_C-EUC0603"))
    )
    (comp (ref "C303")
      (value "DNP")
      (footprint "eagle-import:C0603")
      (libsource (lib "eagle-import") (part "rcl_334_C-EUC0603"))
    )
    (comp (ref "C304")
      (value "DNP")
      (footprint "eagle-import:C0603")
      (libsource (lib "eagle-import") (part "rcl_334_C-EUC0603"))
    )
    (comp (ref "C305")
      (value "DNP")
      (footprint "eagle-import:C0603")
      (libsource (lib "eagle-import") (part "rcl_334_C-EUC0603"))
    )
    (comp (ref "D301")
      (value "BAS70-04")
      (footprint "eagle-import:SOT23")
      (fields (field (name "MODEL") "1SS374"))
      (libsource (lib "eagle-import") (part "BAS70-04"))
    )
    (comp (ref "D302")
      (value "BAS70-04")
      (footprint "eagle-import:SOT23")
      (fields (field (name "MODEL") "1SS374"))
      (libsource (lib "eagle-import") (part "BAS70-04"))
    )
    (comp (ref "D303")
      (value "BAS70-04")
      (footprint "eagle-import:SOT23")
      (fields (field (name "MODEL") "1SS374"))
      (libsource (lib "eagle-import") (part "BAS70-04"))
    )
    (comp (ref "R301")
      (value "0")
      (footprint "eagle-import:R0603")
      (libsource (lib "eagle-import") (part "R-US_R0603"))
    )
    (comp (ref "R302")
      (value "0")
      (footprint "eagle-import:R0603")
      (libsource (lib "eagle-import") (part "R-US_R0603"))
    )
    (comp (ref "R303")
      (value "0")
      (footprint "eagle-import:R0603")
      (libsource (lib "eagle-import") (part "R-US_R0603"))
    )
    (comp (ref "R304")
      (value "100")
      (footprint "eagle-import:R0603")
      (libsource (lib "eagle-import") (part "R-US_R0603"))
    )
    (comp (ref "R305")
      (value "100")
      (footprint "eagle-import:R0603")
      (libsource (lib "eagle-import") (part "R-US_R0603"))
    )
    (comp (ref "R306")
      (value "470")
      (footprint "eagle-import:R0603")
      (libsource (lib "eagle-import") (part "R-US_R0603"))
    )
    (comp (ref "R307")
      (value "DNP")
      (footprint "eagle-import:R0603")
      (libsource (lib "eagle-import") (part "R-US_R0603"))
    )
    (comp (ref "R308")
      (value "DNP")
      (footprint "eagle-import:R0603")
      (libsource (lib "eagle-import") (part "R-US_R0603"))
    )
    (comp (ref "R309")
      (value "DNP")
      (footprint "eagle-import:R0603")
      (libsource (lib "eagle-import") (part "R-US_R0603"))
    )
    (comp (ref "U300")
      (value "TLE5012B")
      (footprint "eagle-import:PG-DSO-8")
      (fields (field (name "MODEL") "TLE5012B"))
      (libsource (lib "eagle-import") (part "TLE5012B"))
    )
    (comp (ref "C1")
      (value ".1nF")
      (footprint "eagle-import:C0603")
      (libsource (lib "eagle-import") (part "rcl_334_C-EUC0603"))
    )
    (comp (ref "C2")
      (value ".1nF")
      (footprint "eagle-import:C0603")
      (libsource (lib "eagle-import") (part "rcl_334_C-EUC0603"))
    )
    (comp (ref "D1")
      (value "MBR0520LT1G")
      (footprint "eagle-import:SODFL3718X115")
      (fields (field (name "MANUFACTURER") "ON Semiconductor") (field (name "MODEL") "MBR0520LT1G"))
      (libsource (lib "eagle-import") (part "SCHOTTKY_DO-219MBR0520LT1G"))
    )
    (comp (ref "D2")
      (value "MBR0520LT1G")
      (footprint "eagle-import:SODFL3718X115")
      (fields (field (name "MANUFACTURER") "ON Semiconductor") (field (name "MODEL") "MBR0520LT1G"))
      (libsource (lib "eagle-import") (part "SCHOTTKY_DO-219MBR0520LT1G"))
    )
    (comp (ref "D5V_ENC")
      (value "LEDCHIPLED_0805")
      (footprint "eagle-import:CHIPLED_0805")
      (libsource (lib "eagle-import") (part "LEDCHIPLED_0805"))
    )
    (comp (ref "D6")
      (value "MBR0520LT1G")
      (footprint "eagle-import:SODFL3718X115")
      (fields (field (name "MANUFACTURER") "ON Semiconductor") (field (name "MODEL") "MBR0520LT1G"))
      (libsource (lib "eagle-import") (part "SCHOTTKY_DO-219MBR0520LT1G"))
    )
    (comp (ref "D12V")
      (value "LEDCHIPLED_0805")
      (footprint "eagle-import:CHIPLED_0805")
      (libsource (lib "eagle-import") (part "LEDCHIPLED_0805"))
    )
    (comp (ref "F1")
      (value "0679L3000")
      (footprint "eagle-import:2410(6125METRIC)")
      (libsource (lib "eagle-import") (part "0679L-FUSE"))
    )
    (comp (ref "F2")
      (value "0679L0250")
      (footprint "eagle-import:2410(6125METRIC)")
      (libsource (lib "eagle-import") (part "0679L-FUSE"))
    )
    (comp (ref "F3")
      (value "0679L0250")
      (footprint "eagle-import:2410(6125METRIC)")
      (libsource (lib "eagle-import") (part "0679L-FUSE"))
    )
    (comp (ref "JD04")
      (value "6620XX21122_66201621122")
      (footprint "eagle-import:66201621122")
      (fields (field (name "MODEL") "66201621122"))
      (libsource (lib "eagle-import") (part "6620XX21122_66201621122"))
    )
    (comp (ref "JDPH")
      (value "6620XX21122_66200421122")
      (footprint "eagle-import:66200421122")
      (fields (field (name "MODEL") "66200421122"))
      (libsource (lib "eagle-import") (part "6620XX21122_66200421122"))
    )
    (comp (ref "JPROG")
      (value "TC2050-IDC")
      (footprint "eagle-import:TC2050-IDC")
      (libsource (lib "eagle-import") (part "TC2050-IDC"))
    )
    (comp (ref "JSOL")
      (value "6620XX11122_66200211122")
      (footprint "eagle-import:66200211122")
      (fields (field (name "MODEL") "66200211122"))
      (libsource (lib "eagle-import") (part "6620XX11122_66200211122"))
    )
    (comp (ref "JTEMP")
      (value "6620XX21122_66200421122")
      (footprint "eagle-import:66200421122")
      (fields (field (name "MODEL") "66200421122"))
      (libsource (lib "eagle-import") (part "6620XX21122_66200421122"))
    )
    (comp (ref "R1")
      (value "1M")
      (footprint "eagle-import:R0603")
      (libsource (lib "eagle-import") (part "R-US_R0603"))
    )
    (comp (ref "R2")
      (value "10k")
      (footprint "eagle-import:R0603")
      (libsource (lib "eagle-import") (part "R-US_R0603"))
    )
    (comp (ref "R3")
      (value "10k")
      (footprint "eagle-import:R0603")
      (libsource (lib "eagle-import") (part "R-US_R0603"))
    )
    (comp (ref "R5")
      (value "10k")
      (footprint "eagle-import:R0603")
      (libsource (lib "eagle-import") (part "R-US_R0603"))
    )
    (comp (ref "R6")
      (value "10k")
      (footprint "eagle-import:R0603")
      (libsource (lib "eagle-import") (part "R-US_R0603"))
    )
    (comp (ref "R8")
      (value "100")
      (footprint "eagle-import:R0603")
      (libsource (lib "eagle-import") (part "R-US_R0603"))
    )
    (comp (ref "TVS1")
      (value "SM15T18AY")
      (footprint "eagle-import:SMC")
      (libsource (lib "eagle-import") (part "SM15TY"))
    )
    (comp (ref "TVS2")
      (value "SM15T6V8AY")
      (footprint "eagle-import:SMC")
      (libsource (lib "eagle-import") (part "SM15TY"))
    )
    (comp (ref "TVS3")
      (value "BAS70-04")
      (footprint "eagle-import:SOT23")
      (fields (field (name "MODEL") "1SS374"))
      (libsource (lib "eagle-import") (part "BAS70-04"))
    )
    (comp (ref "C601")
      (value "22uF")
      (footprint "eagle-import:C0603")
      (libsource (lib "eagle-import") (part "rcl_334_C-EUC0603"))
    )
    (comp (ref "C602")
      (value "22uF")
      (footprint "eagle-import:C0603")
      (libsource (lib "eagle-import") (part "rcl_334_C-EUC0603"))
    )
    (comp (ref "C603")
      (value "22uF")
      (footprint "eagle-import:C0603")
      (libsource (lib "eagle-import") (part "rcl_334_C-EUC0603"))
    )
    (comp (ref "C604")
      (value "22uF")
      (footprint "eagle-import:C0603")
      (libsource (lib "eagle-import") (part "rcl_334_C-EUC0603"))
    )
    (comp (ref "C605")
      (value "3.3nF")
      (footprint "eagle-import:C0603")
      (libsource (lib "eagle-import") (part "rcl_334_C-EUC0603"))
    )
    (comp (ref "C606")
      (value "4.7uF")
      (footprint "eagle-import:C0603")
      (libsource (lib "eagle-import") (part "rcl_334_C-EUC0603"))
    )
    (comp (ref "C607")
      (value "47uF")
      (footprint "eagle-import:C1210")
      (libsource (lib "eagle-import") (part "rcl_334_C-EUC1210"))
    )
    (comp (ref "C608")
      (value "47uF")
      (footprint "eagle-import:C1210")
      (libsource (lib "eagle-import") (part "rcl_334_C-EUC1210"))
    )
    (comp (ref "C609")
      (value "4.7nF")
      (footprint "eagle-import:C0603")
      (libsource (lib "eagle-import") (part "rcl_334_C-EUC0603"))
    )
    (comp (ref "C610")
      (value "12pF")
      (footprint "eagle-import:C0603")
      (libsource (lib "eagle-import") (part "rcl_334_C-EUC0603"))
    )
    (comp (ref "C611")
      (value "10uF")
      (footprint "eagle-import:C0603")
      (libsource (lib "eagle-import") (part "rcl_334_C-EUC0603"))
    )
    (comp (ref "C612")
      (value "0.1uF")
      (footprint "eagle-import:C0603")
      (libsource (lib "eagle-import") (part "rcl_334_C-EUC0603"))
    )
    (comp (ref "D3V3")
      (value "LEDCHIPLED_0805")
      (footprint "eagle-import:CHIPLED_0805")
      (libsource (lib "eagle-import") (part "LEDCHIPLED_0805"))
    )
    (comp (ref "D5V")
      (value "LEDCHIPLED_0805")
      (footprint "eagle-import:CHIPLED_0805")
      (libsource (lib "eagle-import") (part "LEDCHIPLED_0805"))
    )
    (comp (ref "D601")
      (value "SL44")
      (footprint "eagle-import:DO-214AB")
      (fields (field (name "MODEL") "SL44-E3/57T "))
      (libsource (lib "eagle-import") (part "SL44"))
    )
    (comp (ref "L601")
      (value "XAL5030")
      (footprint "eagle-import:XAL5030")
      (fields (field (name "MODEL") "XAL5030-332ME"))
      (libsource (lib "eagle-import") (part "XAL5030"))
    )
    (comp (ref "R601")
      (value "10k")
      (footprint "eagle-import:R0603")
      (libsource (lib "eagle-import") (part "R-US_R0603"))
    )
    (comp (ref "R602")
      (value "10k")
      (footprint "eagle-import:R0603")
      (libsource (lib "eagle-import") (part "R-US_R0603"))
    )
    (comp (ref "R603")
      (value "47k")
      (footprint "eagle-import:R0603")
      (libsource (lib "eagle-import") (part "R-US_R0603"))
    )
    (comp (ref "R604")
      (value "22k")
      (footprint "eagle-import:R0603")
      (libsource (lib "eagle-import") (part "R-US_R0603"))
    )
    (comp (ref "R605")
      (value "10k")
      (footprint "eagle-import:R0603")
      (libsource (lib "eagle-import") (part "R-US_R0603"))
    )
    (comp (ref "R606")
      (value "56.25k")
      (footprint "eagle-import:R0603")
      (libsource (lib "eagle-import") (part "R-US_R0603"))
    )
    (comp (ref "R607")
      (value "10k")
      (footprint "eagle-import:R0603")
      (libsource (lib "eagle-import") (part "R-US_R0603"))
    )
    (comp (ref "R608")
      (value "95.3k")
      (footprint "eagle-import:R0603")
      (libsource (lib "eagle-import") (part "R-US_R0603"))
    )
    (comp (ref "R609")
      (value "18k")
      (footprint "eagle-import:R0603")
      (libsource (lib "eagle-import") (part "R-US_R0603"))
    )
    (comp (ref "R610")
      (value "DNP")
      (footprint "eagle-import:R0603")
      (libsource (lib "eagle-import") (part "R-US_R0603"))
    )
    (comp (ref "R705")
      (value "10k")
      (footprint "eagle-import:R0603")
      (libsource (lib "eagle-import") (part "R-US_R0603"))
    )
    (comp (ref "U600")
      (value "TPS65321-Q1")
      (footprint "eagle-import:14-HTSSOP")
      (libsource (lib "eagle-import") (part "TPS65321-Q1"))
    )
    (comp (ref "C901")
      (value "22uF")
      (footprint "eagle-import:C1206")
      (libsource (lib "eagle-import") (part "rcl_334_C-EUC1206"))
    )
    (comp (ref "D901")
      (value "MBR0520LT1G")
      (footprint "eagle-import:SODFL3718X115")
      (fields (field (name "MANUFACTURER") "ON Semiconductor") (field (name "MODEL") "MBR0520LT1G "))
      (libsource (lib "eagle-import") (part "SCHOTTKY_DO-219MBR0520LT1G"))
    )
    (comp (ref "DSOL")
      (value "LEDCHIPLED_0805")
      (footprint "eagle-import:CHIPLED_0805")
      (libsource (lib "eagle-import") (part "LEDCHIPLED_0805"))
    )
    (comp (ref "QN901")
      (value "FDV305N")
      (footprint "eagle-import:SOT323-3_NFET")
      (fields (field (name "MODEL") "FDV305N"))
      (libsource (lib "eagle-import") (part "NFET"))
    )
    (comp (ref "QP901")
      (value "ZXM61P02FTA")
      (footprint "eagle-import:SOT323-3_NFET")
      (fields (field (name "MODEL") "PMV35EPER"))
      (libsource (lib "eagle-import") (part "NFET"))
    )
    (comp (ref "R901")
      (value "10k")
      (footprint "eagle-import:R0603")
      (libsource (lib "eagle-import") (part "rcl_334_R-US_R0603"))
    )
    (comp (ref "R902")
      (value "10k")
      (footprint "eagle-import:R0603")
      (libsource (lib "eagle-import") (part "rcl_334_R-US_R0603"))
    )
    (comp (ref "R903")
      (value "10k")
      (footprint "eagle-import:R0603")
      (libsource (lib "eagle-import") (part "rcl_334_R-US_R0603"))
    )
  )
  (nets
    (net (code "1") (name "+3V3") (class "Default")
      (node (ref "C103") (pin "1") (pinfunction "1_1") (pintype "passive"))
      (node (ref "C104") (pin "1") (pinfunction "1_1") (pintype "passive"))
      (node (ref "C107") (pin "1") (pinfunction "1_1") (pintype "passive"))
      (node (ref "C108") (pin "1") (pinfunction "1_1") (pintype "passive"))
      (node (ref "C109") (pin "1") (pinfunction "1_1") (pintype "passive"))
      (node (ref "C110") (pin "1") (pinfunction "1_1") (pintype "passive"))
      (node (ref "C201") (pin "1") (pinfunction "1_1") (pintype "passive"))
      (node (ref "C401") (pin "1") (pinfunction "1_1") (pintype "passive"))
      (node (ref "C402") (pin "1") (pinfunction "1_1") (pintype "passive"))
      (node (ref "C502") (pin "1") (pinfunction "1_1") (pintype "passive"))
      (node (ref "C503") (pin "1") (pinfunction "1_1") (pintype "passive"))
      (node (ref "C611") (pin "1") (pinfunction "1_1") (pintype "passive"))
      (node (ref "D6") (pin "1") (pinfunction "C_1") (pintype "passive"))
      (node (ref "JTEMP") (pin "3") (pinfunction "3_3") (pintype "passive"))
      (node (ref "R209") (pin "2") (pinfunction "2_2") (pintype "passive"))
      (node (ref "R210") (pin "2") (pinfunction "2_2") (pintype "passive"))
      (node (ref "R211") (pin "1") (pinfunction "1_1") (pintype "passive"))
      (node (ref "R212") (pin "1") (pinfunction "1_1") (pintype "passive"))
      (node (ref "R608") (pin "2") (pinfunction "2_2") (pintype "passive"))
      (node (ref "R705") (pin "2") (pinfunction "2_2") (pintype "passive"))
      (node (ref "TVS801") (pin "2") (pinfunction "C2_2") (pintype "passive"))
      (node (ref "U100") (pin "1") (pinfunction "VBAT_1") (pintype "power_in"))
      (node (ref "U100") (pin "13") (pinfunction "VDDA_13") (pintype "power_in"))
      (node (ref "U100") (pin "19") (pinfunction "VDD_19") (pintype "power_in"))
      (node (ref "U100") (pin "32") (pinfunction "VDD_32") (pintype "power_in"))
      (node (ref "U100") (pin "48") (pinfunction "VDD_48") (pintype "power_in"))
      (node (ref "U100") (pin "64") (pinfunction "VDD_64") (pintype "power_in"))
      (node (ref "U200") (pin "5") (pinfunction "VIO_5") (pintype "bidirectional"))
      (node (ref "U400") (pin "P5") (pinfunction "P5_VDD_P5") (pintype "power_in"))
      (node (ref "U500") (pin "13") (pinfunction "VDD_13") (pintype "bidirectional"))
      (node (ref "U500") (pin "8") (pinfunction "VDDIO_8") (pintype "bidirectional"))
      (node (ref "U600") (pin "P4") (pinfunction "LDO_OUT_P4") (pintype "bidirectional"))
    )
    (net (code "2") (name "+5V") (class "Default")
      (node (ref "C203") (pin "1") (pinfunction "1_1") (pintype "passive"))
      (node (ref "C204") (pin "1") (pinfunction "1_1") (pintype "passive"))
      (node (ref "C606") (pin "1") (pinfunction "1_1") (pintype "passive"))
      (node (ref "C607") (pin "1") (pinfunction "1_1") (pintype "passive"))
      (node (ref "C608") (pin "1") (pinfunction "1_1") (pintype "passive"))
      (node (ref "L601") (pin "P2") (pinfunction "P$2_P2") (pintype "bidirectional"))
      (node (ref "R605") (pin "2") (pinfunction "2_2") (pintype "passive"))
      (node (ref "R606") (pin "2") (pinfunction "2_2") (pintype "passive"))
      (node (ref "U200") (pin "3") (pinfunction "VCC_3") (pintype "bidirectional"))
      (node (ref "U600") (pin "P3") (pinfunction "VIN_LDO_P3") (pintype "bidirectional"))
    )
    (net (code "3") (name "+5V{slash}1") (class "Default")
      (node (ref "C301") (pin "1") (pinfunction "1_1") (pintype "passive"))
      (node (ref "C302") (pin "1") (pinfunction "1_1") (pintype "passive"))
      (node (ref "D2") (pin "1") (pinfunction "C_1") (pintype "passive"))
      (node (ref "D301") (pin "2") (pinfunction "C2_2") (pintype "passive"))
      (node (ref "D302") (pin "2") (pinfunction "C2_2") (pintype "passive"))
      (node (ref "D303") (pin "2") (pinfunction "C2_2") (pintype "passive"))
      (node (ref "R307") (pin "2") (pinfunction "2_2") (pintype "passive"))
      (node (ref "R308") (pin "2") (pinfunction "2_2") (pintype "passive"))
      (node (ref "R309") (pin "2") (pinfunction "2_2") (pintype "passive"))
      (node (ref "R6") (pin "2") (pinfunction "2_2") (pintype "passive"))
      (node (ref "U300") (pin "P6") (pinfunction "VDD_P6") (pintype "bidirectional"))
    )
    (net (code "4") (name "+12V") (class "Default")
      (node (ref "C601") (pin "1") (pinfunction "1_1") (pintype "passive"))
      (node (ref "C602") (pin "1") (pinfunction "1_1") (pintype "passive"))
      (node (ref "C603") (pin "1") (pinfunction "1_1") (pintype "passive"))
      (node (ref "C604") (pin "1") (pinfunction "1_1") (pintype "passive"))
      (node (ref "C901") (pin "1") (pinfunction "1_1") (pintype "passive"))
      (node (ref "D1") (pin "1") (pinfunction "C_1") (pintype "passive"))
      (node (ref "F1") (pin "P1") (pinfunction "P$1_P1") (pintype "power_in"))
      (node (ref "JDPH") (pin "1") (pinfunction "1_1") (pintype "passive"))
      (node (ref "QP901") (pin "S") (pinfunction "S_S") (pintype "bidirectional"))
      (node (ref "R5") (pin "2") (pinfunction "2_2") (pintype "passive"))
      (node (ref "R601") (pin "2") (pinfunction "2_2") (pintype "passive"))
      (node (ref "R602") (pin "2") (pinfunction "2_2") (pintype "passive"))
      (node (ref "R901") (pin "2") (pinfunction "2_2") (pintype "passive"))
      (node (ref "TVS1") (pin "P$2") (pinfunction "P$2_P$2") (pintype "bidirectional"))
      (node (ref "TVS3") (pin "2") (pinfunction "C2_2") (pintype "passive"))
      (node (ref "U600") (pin "P2") (pinfunction "VIN_P2") (pintype "bidirectional"))
    )
    (net (code "5") (name "+12VCC") (class "Default")
      (node (ref "D901") (pin "1") (pinfunction "C_1") (pintype "passive"))
      (node (ref "JSOL") (pin "2") (pinfunction "2_2") (pintype "passive"))
      (node (ref "QP901") (pin "D") (pinfunction "D_D") (pintype "bidirectional"))
      (node (ref "R903") (pin "2") (pinfunction "2_2") (pintype "passive"))
    )
    (net (code "6") (name "+M1TEMP") (class "Default")
      (node (ref "JD04") (pin "6") (pinfunction "6_6") (pintype "passive"))
      (node (ref "JTEMP") (pin "1") (pinfunction "1_1") (pintype "passive"))
    )
    (net (code "7") (name "-M1TEMP") (class "Default")
      (node (ref "JD04") (pin "7") (pinfunction "7_7") (pintype "passive"))
      (node (ref "JTEMP") (pin "2") (pinfunction "2_2") (pintype "passive"))
    )
    (net (code "8") (name "-M2TEMP") (class "Default")
      (node (ref "JTEMP") (pin "4") (pinfunction "4_4") (pintype "passive"))
      (node (ref "R801") (pin "1") (pinfunction "1_1") (pintype "passive"))
      (node (ref "R802") (pin "1") (pinfunction "1_1") (pintype "passive"))
      (node (ref "TVS801") (pin "3") (pinfunction "C1A2_3") (pintype "passive"))
    )
    (net (code "9") (name "BOOT0") (class "Default")
      (node (ref "JPROG") (pin "5") (pinfunction "5_5") (pintype "passive"))
      (node (ref "R102") (pin "1") (pinfunction "1_1") (pintype "passive"))
      (node (ref "U100") (pin "60") (pinfunction "BOOT0_60") (pintype "input"))
    )
    (net (code "10") (name "CANH") (class "Default")
      (node (ref "D201") (pin "2") (pinfunction "P2_2") (pintype "bidirectional"))
      (node (ref "JD04") (pin "4") (pinfunction "4_4") (pintype "passive"))
      (node (ref "R201") (pin "2") (pinfunction "2_2") (pintype "passive"))
      (node (ref "R203") (pin "2") (pinfunction "2_2") (pintype "passive"))
      (node (ref "U200") (pin "7") (pinfunction "CANH_7") (pintype "bidirectional"))
    )
    (net (code "11") (name "CANL") (class "Default")
      (node (ref "D201") (pin "1") (pinfunction "P1_1") (pintype "bidirectional"))
      (node (ref "JD04") (pin "5") (pinfunction "5_5") (pintype "passive"))
      (node (ref "R202") (pin "1") (pinfunction "1_1") (pintype "passive"))
      (node (ref "R203") (pin "1") (pinfunction "1_1") (pintype "passive"))
      (node (ref "U200") (pin "6") (pinfunction "CANL_6") (pintype "bidirectional"))
    )
    (net (code "12") (name "CSQ") (class "Default")
      (node (ref "JD04") (pin "10") (pinfunction "10_10") (pintype "passive"))
      (node (ref "R304") (pin "2") (pinfunction "2_2") (pintype "passive"))
    )
    (net (code "13") (name "DATA") (class "Default")
      (node (ref "JD04") (pin "11") (pinfunction "11_11") (pintype "passive"))
      (node (ref "R306") (pin "2") (pinfunction "2_2") (pintype "passive"))
    )
    (net (code "14") (name "GND") (class "Default")
      (node (ref "C1") (pin "2") (pinfunction "2_2") (pintype "passive"))
      (node (ref "C101") (pin "2") (pinfunction "2_2") (pintype "passive"))
      (node (ref "C102") (pin "2") (pinfunction "2_2") (pintype "passive"))
      (node (ref "C103") (pin "2") (pinfunction "2_2") (pintype "passive"))
      (node (ref "C104") (pin "2") (pinfunction "2_2") (pintype "passive"))
      (node (ref "C105") (pin "2") (pinfunction "2_2") (pintype "passive"))
      (node (ref "C106") (pin "2") (pinfunction "2_2") (pintype "passive"))
      (node (ref "C107") (pin "2") (pinfunction "2_2") (pintype "passive"))
      (node (ref "C108") (pin "2") (pinfunction "2_2") (pintype "passive"))
      (node (ref "C109") (pin "2") (pinfunction "2_2") (pintype "passive"))
      (node (ref "C110") (pin "2") (pinfunction "2_2") (pintype "passive"))
      (node (ref "C2") (pin "2") (pinfunction "2_2") (pintype "passive"))
      (node (ref "C201") (pin "2") (pinfunction "2_2") (pintype "passive"))
      (node (ref "C202") (pin "2") (pinfunction "2_2") (pintype "passive"))
      (node (ref "C203") (pin "2") (pinfunction "2_2") (pintype "passive"))
      (node (ref "C204") (pin "2") (pinfunction "2_2") (pintype "passive"))
      (node (ref "C401") (pin "2") (pinfunction "2_2") (pintype "passive"))
      (node (ref "C402") (pin "2") (pinfunction "2_2") (pintype "passive"))
      (node (ref "C501") (pin "2") (pinfunction "2_2") (pintype "passive"))
      (node (ref "C502") (pin "2") (pinfunction "2_2") (pintype "passive"))
      (node (ref "C503") (pin "2") (pinfunction "2_2") (pintype "passive"))
      (node (ref "C601") (pin "2") (pinfunction "2_2") (pintype "passive"))
      (node (ref "C602") (pin "2") (pinfunction "2_2") (pintype "passive"))
      (node (ref "C603") (pin "2") (pinfunction "2_2") (pintype "passive"))
      (node (ref "C604") (pin "2") (pinfunction "2_2") (pintype "passive"))
      (node (ref "C605") (pin "2") (pinfunction "2_2") (pintype "passive"))
      (node (ref "C606") (pin "2") (pinfunction "2_2") (pintype "passive"))
      (node (ref "C607") (pin "2") (pinfunction "2_2") (pintype "passive"))
      (node (ref "C608") (pin "2") (pinfunction "2_2") (pintype "passive"))
      (node (ref "C609") (pin "2") (pinfunction "2_2") (pintype "passive"))
      (node (ref "C610") (pin "2") (pinfunction "2_2") (pintype "passive"))
      (node (ref "C611") (pin "2") (pinfunction "2_2") (pintype "passive"))
      (node (ref "C801") (pin "2") (pinfunction "2_2") (pintype "passive"))
      (node (ref "C901") (pin "2") (pinfunction "2_2") (pintype "passive"))
      (node (ref "D12V") (pin "C") (pinfunction "C_C") (pintype "passive"))
      (node (ref "D201") (pin "3") (pinfunction "P3_3") (pintype "bidirectional"))
      (node (ref "D3V3") (pin "C") (pinfunction "C_C") (pintype "passive"))
      (node (ref "D5V") (pin "C") (pinfunction "C_C") (pintype "passive"))
      (node (ref "D601") (pin "ANODE") (pinfunction "ANODE_ANODE") (pintype "bidirectional"))
      (node (ref "D901") (pin "2") (pinfunction "A_2") (pintype "passive"))
      (node (ref "DB0") (pin "C") (pinfunction "C_C") (pintype "passive"))
      (node (ref "DB1") (pin "C") (pinfunction "C_C") (pintype "passive"))
      (node (ref "DBOOT1") (pin "C") (pinfunction "C_C") (pintype "passive"))
      (node (ref "DSOL") (pin "C") (pinfunction "C_C") (pintype "passive"))
      (node (ref "JD04") (pin "2") (pinfunction "2_2") (pintype "passive"))
      (node (ref "JDPH") (pin "3") (pinfunction "3_3") (pintype "passive"))
      (node (ref "JDPH") (pin "4") (pinfunction "4_4") (pintype "passive"))
      (node (ref "JPROG") (pin "3") (pinfunction "3_3") (pintype "passive"))
      (node (ref "JSOL") (pin "1") (pinfunction "1_1") (pintype "passive"))
      (node (ref "QN901") (pin "S") (pinfunction "S_S") (pintype "bidirectional"))
      (node (ref "R1") (pin "2") (pinfunction "2_2") (pintype "passive"))
      (node (ref "R102") (pin "2") (pinfunction "2_2") (pintype "passive"))
      (node (ref "R104") (pin "2") (pinfunction "2_2") (pintype "passive"))
      (node (ref "R204") (pin "1") (pinfunction "1_1") (pintype "passive"))
      (node (ref "R206") (pin "2") (pinfunction "2_2") (pintype "passive"))
      (node (ref "R208") (pin "2") (pinfunction "2_2") (pintype "passive"))
      (node (ref "R3") (pin "2") (pinfunction "2_2") (pintype "passive"))
      (node (ref "R603") (pin "1") (pinfunction "1_1") (pintype "passive"))
      (node (ref "R607") (pin "1") (pinfunction "1_1") (pintype "passive"))
      (node (ref "R609") (pin "1") (pinfunction "1_1") (pintype "passive"))
      (node (ref "R801") (pin "2") (pinfunction "2_2") (pintype "passive"))
      (node (ref "R902") (pin "1") (pinfunction "1_1") (pintype "passive"))
      (node (ref "TVS1") (pin "P$1") (pinfunction "P$1_P$1") (pintype "bidirectional"))
      (node (ref "TVS2") (pin "P$1") (pinfunction "P$1_P$1") (pintype "bidirectional"))
      (node (ref "TVS3") (pin "1") (pinfunction "A1_1") (pintype "passive"))
      (node (ref "TVS801") (pin "1") (pinfunction "A1_1") (pintype "passive"))
      (node (ref "U100") (pin "12") (pinfunction "VSSA_12") (pintype "power_in"))
      (node (ref "U100") (pin "18") (pinfunction "VSS_18") (pintype "power_in"))
      (node (ref "U100") (pin "31") (pinfunction "VSS_31") (pintype "power_in"))
      (node (ref "U100") (pin "47") (pinfunction "VSS_47") (pintype "power_in"))
      (node (ref "U100") (pin "63") (pinfunction "VSS_63") (pintype "power_in"))
      (node (ref "U200") (pin "2") (pinfunction "GND_2") (pintype "bidirectional"))
      (node (ref "U400") (pin "P2") (pinfunction "P2_GND_P2") (pintype "power_in"))
      (node (ref "U500") (pin "18") (pinfunction "GND_18") (pintype "bidirectional"))
      (node (ref "U500") (pin "19") (pinfunction "INT2_19") (pintype "bidirectional"))
      (node (ref "U500") (pin "20") (pinfunction "GND_20") (pintype "bidirectional"))
      (node (ref "U600") (pin "P13") (pinfunction "GND_P13") (pintype "bidirectional"))
      (node (ref "U600") (pin "P15") (pinfunction "PWR_PAD_P15") (pintype "bidirectional"))
      (node (ref "U600") (pin "P16") (pinfunction "PWR_PAD_P16") (pintype "bidirectional"))
      (node (ref "U600") (pin "P17") (pinfunction "PWR_PAD_P17") (pintype "bidirectional"))
      (node (ref "U600") (pin "P18") (pinfunction "PWR_PAD_P18") (pintype "bidirectional"))
      (node (ref "U600") (pin "P19") (pinfunction "PWR_PAD_P19") (pintype "bidirectional"))
      (node (ref "U600") (pin "P20") (pinfunction "PWR_PAD_P20") (pintype "bidirectional"))
      (node (ref "U600") (pin "P21") (pinfunction "PWR_PAD_P21") (pintype "bidirectional"))
      (node (ref "U600") (pin "P22") (pinfunction "PWR_PAD_P22") (pintype "bidirectional"))
      (node (ref "U600") (pin "P23") (pinfunction "PWR_PAD_P23") (pintype "bidirectional"))
    )
    (net (code "15") (name "GND1") (class "Default")
      (node (ref "C301") (pin "2") (pinfunction "2_2") (pintype "passive"))
      (node (ref "C302") (pin "2") (pinfunction "2_2") (pintype "passive"))
      (node (ref "C303") (pin "2") (pinfunction "2_2") (pintype "passive"))
      (node (ref "C304") (pin "2") (pinfunction "2_2") (pintype "passive"))
      (node (ref "C305") (pin "2") (pinfunction "2_2") (pintype "passive"))
      (node (ref "D301") (pin "1") (pinfunction "A1_1") (pintype "passive"))
      (node (ref "D302") (pin "1") (pinfunction "A1_1") (pintype "passive"))
      (node (ref "D303") (pin "1") (pinfunction "A1_1") (pintype "passive"))
      (node (ref "D5V_ENC") (pin "C") (pinfunction "C_C") (pintype "passive"))
      (node (ref "JD04") (pin "16") (pinfunction "16_16") (pintype "passive"))
      (node (ref "U300") (pin "P7") (pinfunction "GND_P7") (pintype "bidirectional"))
    )
    (net (code "16") (name "ID-BIT0") (class "Default")
      (node (ref "ID-BIT0") (pin "2") (pinfunction "2_2") (pintype "passive"))
      (node (ref "R207") (pin "1") (pinfunction "1_1") (pintype "passive"))
    )
    (net (code "17") (name "ID-BIT1") (class "Default")
      (node (ref "ID-BIT1") (pin "2") (pinfunction "2_2") (pintype "passive"))
      (node (ref "R205") (pin "1") (pinfunction "1_1") (pintype "passive"))
    )
    (net (code "18") (name "IFA") (class "Default")
      (node (ref "C303") (pin "1") (pinfunction "1_1") (pintype "passive"))
      (node (ref "D303") (pin "3") (pinfunction "C1A2_3") (pintype "passive"))
      (node (ref "JD04") (pin "12") (pinfunction "12_12") (pintype "passive"))
      (node (ref "R301") (pin "2") (pinfunction "2_2") (pintype "passive"))
    )
    (net (code "19") (name "IFB") (class "Default")
      (node (ref "C304") (pin "1") (pinfunction "1_1") (pintype "passive"))
      (node (ref "D302") (pin "3") (pinfunction "C1A2_3") (pintype "passive"))
      (node (ref "JD04") (pin "13") (pinfunction "13_13") (pintype "passive"))
      (node (ref "R302") (pin "2") (pinfunction "2_2") (pintype "passive"))
    )
    (net (code "20") (name "IFC") (class "Default")
      (node (ref "C305") (pin "1") (pinfunction "1_1") (pintype "passive"))
      (node (ref "D301") (pin "3") (pinfunction "C1A2_3") (pintype "passive"))
      (node (ref "JD04") (pin "14") (pinfunction "14_14") (pintype "passive"))
      (node (ref "R303") (pin "2") (pinfunction "2_2") (pintype "passive"))
    )
    (net (code "21") (name "Net-(C102-Pad1)") (class "Default")
      (node (ref "C102") (pin "1") (pinfunction "1_1") (pintype "passive"))
      (node (ref "Q1") (pin "1") (pinfunction "1_1") (pintype "passive"))
      (node (ref "R101") (pin "1") (pinfunction "1_1") (pintype "passive"))
    )
    (net (code "22") (name "Net-(C202-Pad1)") (class "Default")
      (node (ref "C202") (pin "1") (pinfunction "1_1") (pintype "passive"))
      (node (ref "R201") (pin "1") (pinfunction "1_1") (pintype "passive"))
      (node (ref "R202") (pin "2") (pinfunction "2_2") (pintype "passive"))
    )
    (net (code "23") (name "Net-(C609-Pad1)") (class "Default")
      (node (ref "C609") (pin "1") (pinfunction "1_1") (pintype "passive"))
      (node (ref "R604") (pin "1") (pinfunction "1_1") (pintype "passive"))
    )
    (net (code "24") (name "Net-(D2-A)") (class "Default")
      (node (ref "D2") (pin "2") (pinfunction "A_2") (pintype "passive"))
      (node (ref "F2") (pin "P2") (pinfunction "P$2_P2") (pintype "power_in"))
      (node (ref "TVS2") (pin "P$2") (pinfunction "P$2_P$2") (pintype "bidirectional"))
    )
    (net (code "25") (name "Net-(D3V3-PadA)") (class "Default")
      (node (ref "D3V3") (pin "A") (pinfunction "A_A") (pintype "passive"))
      (node (ref "R705") (pin "1") (pinfunction "1_1") (pintype "passive"))
    )
    (net (code "26") (name "Net-(D5V-PadA)") (class "Default")
      (node (ref "D5V") (pin "A") (pinfunction "A_A") (pintype "passive"))
      (node (ref "R605") (pin "1") (pinfunction "1_1") (pintype "passive"))
    )
    (net (code "27") (name "Net-(D5V_ENC-PadA)") (class "Default")
      (node (ref "D5V_ENC") (pin "A") (pinfunction "A_A") (pintype "passive"))
      (node (ref "R6") (pin "1") (pinfunction "1_1") (pintype "passive"))
    )
    (net (code "28") (name "Net-(D6-A)") (class "Default")
      (node (ref "D6") (pin "2") (pinfunction "A_2") (pintype "passive"))
      (node (ref "JPROG") (pin "10") (pinfunction "10_10") (pintype "passive"))
    )
    (net (code "29") (name "Net-(D12V-PadA)") (class "Default")
      (node (ref "D12V") (pin "A") (pinfunction "A_A") (pintype "passive"))
      (node (ref "R5") (pin "1") (pinfunction "1_1") (pintype "passive"))
    )
    (net (code "30") (name "Net-(DB0-PadA)") (class "Default")
      (node (ref "DB0") (pin "A") (pinfunction "A_A") (pintype "passive"))
      (node (ref "R207") (pin "2") (pinfunction "2_2") (pintype "passive"))
    )
    (net (code "31") (name "Net-(DB1-PadA)") (class "Default")
      (node (ref "DB1") (pin "A") (pinfunction "A_A") (pintype "passive"))
      (node (ref "R205") (pin "2") (pinfunction "2_2") (pintype "passive"))
    )
    (net (code "32") (name "Net-(DBOOT1-PadA)") (class "Default")
      (node (ref "DBOOT1") (pin "A") (pinfunction "A_A") (pintype "passive"))
      (node (ref "R103") (pin "2") (pinfunction "2_2") (pintype "passive"))
      (node (ref "R104") (pin "1") (pinfunction "1_1") (pintype "passive"))
    )
    (net (code "33") (name "Net-(DRX-PadA)") (class "Default")
      (node (ref "DRX") (pin "A") (pinfunction "A_A") (pintype "passive"))
      (node (ref "R209") (pin "1") (pinfunction "1_1") (pintype "passive"))
    )
    (net (code "34") (name "Net-(DSOL-PadA)") (class "Default")
      (node (ref "DSOL") (pin "A") (pinfunction "A_A") (pintype "passive"))
      (node (ref "R903") (pin "1") (pinfunction "1_1") (pintype "passive"))
    )
    (net (code "35") (name "Net-(DTX-PadA)") (class "Default")
      (node (ref "DTX") (pin "A") (pinfunction "A_A") (pintype "passive"))
      (node (ref "R210") (pin "1") (pinfunction "1_1") (pintype "passive"))
    )
    (net (code "36") (name "Net-(F1-P$2)") (class "Default")
      (node (ref "F1") (pin "P2") (pinfunction "P$2_P2") (pintype "power_in"))
      (node (ref "JD04") (pin "8") (pinfunction "8_8") (pintype "passive"))
    )
    (net (code "37") (name "Net-(F2-P$1)") (class "Default")
      (node (ref "F2") (pin "P1") (pinfunction "P$1_P1") (pintype "power_in"))
      (node (ref "JD04") (pin "15") (pinfunction "15_15") (pintype "passive"))
    )
    (net (code "38") (name "Net-(F3-P$1)") (class "Default")
      (node (ref "F3") (pin "P1") (pinfunction "P$1_P1") (pintype "power_in"))
      (node (ref "JPROG") (pin "1") (pinfunction "1_1") (pintype "passive"))
    )
    (net (code "39") (name "Net-(ID-BIT0-Pad1)") (class "Default")
      (node (ref "ID-BIT0") (pin "1") (pinfunction "1_1") (pintype "passive"))
      (node (ref "R212") (pin "2") (pinfunction "2_2") (pintype "passive"))
    )
    (net (code "40") (name "Net-(ID-BIT0-Pad3)") (class "Default")
      (node (ref "ID-BIT0") (pin "3") (pinfunction "3_3") (pintype "passive"))
      (node (ref "R208") (pin "1") (pinfunction "1_1") (pintype "passive"))
    )
    (net (code "41") (name "Net-(ID-BIT1-Pad1)") (class "Default")
      (node (ref "ID-BIT1") (pin "1") (pinfunction "1_1") (pintype "passive"))
      (node (ref "R211") (pin "2") (pinfunction "2_2") (pintype "passive"))
    )
    (net (code "42") (name "Net-(ID-BIT1-Pad3)") (class "Default")
      (node (ref "ID-BIT1") (pin "3") (pinfunction "3_3") (pintype "passive"))
      (node (ref "R206") (pin "1") (pinfunction "1_1") (pintype "passive"))
    )
    (net (code "43") (name "Net-(L601-P$1)") (class "Default")
      (node (ref "C612") (pin "1") (pinfunction "1_1") (pintype "passive"))
      (node (ref "D601") (pin "CATHODE") (pinfunction "CATHODE_CATHODE") (pintype "bidirectional"))
      (node (ref "L601") (pin "P1") (pinfunction "P$1_P1") (pintype "bidirectional"))
      (node (ref "U600") (pin "P14") (pinfunction "SW_P14") (pintype "bidirectional"))
    )
    (net (code "44") (name "Net-(Q1-2)") (class "Default")
      (node (ref "C101") (pin "1") (pinfunction "1_1") (pintype "passive"))
      (node (ref "Q1") (pin "3") (pinfunction "2_3") (pintype "passive"))
      (node (ref "U100") (pin "5") (pinfunction "OSC_IN_5") (pintype "bidirectional"))
    )
    (net (code "45") (name "Net-(QN901-PadD)") (class "Default")
      (node (ref "QN901") (pin "D") (pinfunction "D_D") (pintype "bidirectional"))
      (node (ref "QP901") (pin "G") (pinfunction "G_G") (pintype "bidirectional"))
      (node (ref "R901") (pin "1") (pinfunction "1_1") (pintype "passive"))
    )
    (net (code "46") (name "Net-(R2-Pad2)") (class "Default")
      (node (ref "R2") (pin "2") (pinfunction "2_2") (pintype "passive"))
      (node (ref "R3") (pin "1") (pinfunction "1_1") (pintype "passive"))
      (node (ref "R8") (pin "1") (pinfunction "1_1") (pintype "passive"))
    )
    (net (code "47") (name "Net-(U100A-NRST)") (class "Default")
      (node (ref "C105") (pin "1") (pinfunction "1_1") (pintype "passive"))
      (node (ref "U100") (pin "7") (pinfunction "NRST_7") (pintype "bidirectional"))
    )
    (net (code "48") (name "Net-(U100A-OSC_OUT)") (class "Default")
      (node (ref "R101") (pin "2") (pinfunction "2_2") (pintype "passive"))
      (node (ref "U100") (pin "6") (pinfunction "OSC_OUT_6") (pintype "bidirectional"))
    )
    (net (code "49") (name "Net-(U100A-VCAP1)") (class "Default")
      (node (ref "C106") (pin "1") (pinfunction "1_1") (pintype "passive"))
      (node (ref "U100") (pin "30") (pinfunction "VCAP1_30") (pintype "power_in"))
    )
    (net (code "50") (name "Net-(U300-CSQ)") (class "Default")
      (node (ref "R304") (pin "1") (pinfunction "1_1") (pintype "passive"))
      (node (ref "U300") (pin "P3") (pinfunction "CSQ_P3") (pintype "bidirectional"))
    )
    (net (code "51") (name "Net-(U300-DATA)") (class "Default")
      (node (ref "R306") (pin "1") (pinfunction "1_1") (pintype "passive"))
      (node (ref "U300") (pin "P4") (pinfunction "DATA_P4") (pintype "bidirectional"))
    )
    (net (code "52") (name "Net-(U300-IFA)") (class "Default")
      (node (ref "R301") (pin "1") (pinfunction "1_1") (pintype "passive"))
      (node (ref "R307") (pin "1") (pinfunction "1_1") (pintype "passive"))
      (node (ref "U300") (pin "P5") (pinfunction "IFA_P5") (pintype "bidirectional"))
    )
    (net (code "53") (name "Net-(U300-IFB)") (class "Default")
      (node (ref "R302") (pin "1") (pinfunction "1_1") (pintype "passive"))
      (node (ref "R308") (pin "1") (pinfunction "1_1") (pintype "passive"))
      (node (ref "U300") (pin "P8") (pinfunction "IFB_P8") (pintype "bidirectional"))
    )
    (net (code "54") (name "Net-(U300-IFC)") (class "Default")
      (node (ref "R303") (pin "1") (pinfunction "1_1") (pintype "passive"))
      (node (ref "R309") (pin "1") (pinfunction "1_1") (pintype "passive"))
      (node (ref "U300") (pin "P1") (pinfunction "IFC_P1") (pintype "bidirectional"))
    )
    (net (code "55") (name "Net-(U300-SCK)") (class "Default")
      (node (ref "R305") (pin "1") (pinfunction "1_1") (pintype "passive"))
      (node (ref "U300") (pin "P2") (pinfunction "SCK_P2") (pintype "bidirectional"))
    )
    (net (code "56") (name "Net-(U500-REGOUT)") (class "Default")
      (node (ref "C501") (pin "1") (pinfunction "1_1") (pintype "passive"))
      (node (ref "U500") (pin "10") (pinfunction "REGOUT_10") (pintype "bidirectional"))
    )
    (net (code "57") (name "Net-(U600-BOOT)") (class "Default")
      (node (ref "C612") (pin "2") (pinfunction "2_2") (pintype "passive"))
      (node (ref "U600") (pin "P1") (pinfunction "BOOT_P1") (pintype "bidirectional"))
    )
    (net (code "58") (name "Net-(U600-COMP)") (class "Default")
      (node (ref "C610") (pin "1") (pinfunction "1_1") (pintype "passive"))
      (node (ref "R604") (pin "2") (pinfunction "2_2") (pintype "passive"))
      (node (ref "U600") (pin "P12") (pinfunction "COMP_P12") (pintype "bidirectional"))
    )
    (net (code "59") (name "Net-(U600-EN1)") (class "Default")
      (node (ref "R602") (pin "1") (pinfunction "1_1") (pintype "passive"))
      (node (ref "U600") (pin "P8") (pinfunction "EN1_P8") (pintype "bidirectional"))
    )
    (net (code "60") (name "Net-(U600-EN2)") (class "Default")
      (node (ref "R601") (pin "1") (pinfunction "1_1") (pintype "passive"))
      (node (ref "U600") (pin "P7") (pinfunction "EN2_P7") (pintype "bidirectional"))
    )
    (net (code "61") (name "Net-(U600-FB1)") (class "Default")
      (node (ref "R606") (pin "1") (pinfunction "1_1") (pintype "passive"))
      (node (ref "R607") (pin "2") (pinfunction "2_2") (pintype "passive"))
      (node (ref "U600") (pin "P11") (pinfunction "FB1_P11") (pintype "bidirectional"))
    )
    (net (code "62") (name "Net-(U600-FB2)") (class "Default")
      (node (ref "R608") (pin "1") (pinfunction "1_1") (pintype "passive"))
      (node (ref "R609") (pin "2") (pinfunction "2_2") (pintype "passive"))
      (node (ref "U600") (pin "P5") (pinfunction "FB2_P5") (pintype "bidirectional"))
    )
    (net (code "63") (name "Net-(U600-RT{slash}CLK)") (class "Default")
      (node (ref "R603") (pin "2") (pinfunction "2_2") (pintype "passive"))
      (node (ref "U600") (pin "P9") (pinfunction "RT/CLK_P9") (pintype "bidirectional"))
    )
    (net (code "64") (name "Net-(U600-SS)") (class "Default")
      (node (ref "C605") (pin "1") (pinfunction "1_1") (pintype "passive"))
      (node (ref "U600") (pin "P10") (pinfunction "SS_P10") (pintype "bidirectional"))
    )
    (net (code "65") (name "Net-(U600-~{RST})") (class "Default")
      (node (ref "R610") (pin "2") (pinfunction "2_2") (pintype "passive"))
      (node (ref "U600") (pin "P6") (pinfunction "~{RST}_P6") (pintype "bidirectional"))
    )
    (net (code "66") (name "PA3{slash}IMU_INT") (class "Default")
      (node (ref "U100") (pin "17") (pinfunction "PA3_17") (pintype "bidirectional"))
      (node (ref "U500") (pin "12") (pinfunction "INT1_12") (pintype "bidirectional"))
    )
    (net (code "67") (name "PA4{slash}SPI1_CSN") (class "Default")
      (node (ref "U100") (pin "20") (pinfunction "PA4_20") (pintype "bidirectional"))
      (node (ref "U500") (pin "22") (pinfunction "~{CS}_22") (pintype "bidirectional"))
    )
    (net (code "68") (name "PA5{slash}SPI1_SCK") (class "Default")
      (node (ref "U100") (pin "21") (pinfunction "PA5_21") (pintype "bidirectional"))
      (node (ref "U500") (pin "23") (pinfunction "SCL/SCLK_23") (pintype "bidirectional"))
    )
    (net (code "69") (name "PA6{slash}SPI1_MISO") (class "Default")
      (node (ref "U100") (pin "22") (pinfunction "PA6_22") (pintype "bidirectional"))
      (node (ref "U500") (pin "9") (pinfunction "AD0/SD0_9") (pintype "bidirectional"))
    )
    (net (code "70") (name "PA7{slash}SPI1_MOSI") (class "Default")
      (node (ref "U100") (pin "23") (pinfunction "PA7_23") (pintype "bidirectional"))
      (node (ref "U500") (pin "24") (pinfunction "SDA/SDI_24") (pintype "bidirectional"))
    )
    (net (code "71") (name "PA9{slash}USART1_TX") (class "Default")
      (node (ref "JPROG") (pin "2") (pinfunction "2_2") (pintype "passive"))
      (node (ref "U100") (pin "42") (pinfunction "PA9_42") (pintype "bidirectional"))
    )
    (net (code "72") (name "PA10{slash}USART1_RX") (class "Default")
      (node (ref "JPROG") (pin "4") (pinfunction "4_4") (pintype "passive"))
      (node (ref "U100") (pin "43") (pinfunction "PA10_43") (pintype "bidirectional"))
    )
    (net (code "73") (name "PA11{slash}USB_D-") (class "Default")
      (node (ref "JPROG") (pin "8") (pinfunction "8_8") (pintype "passive"))
      (node (ref "U100") (pin "44") (pinfunction "PA11_44") (pintype "bidirectional"))
    )
    (net (code "74") (name "PA12{slash}USB_D+") (class "Default")
      (node (ref "JPROG") (pin "6") (pinfunction "6_6") (pintype "passive"))
      (node (ref "U100") (pin "45") (pinfunction "PA12_45") (pintype "bidirectional"))
    )
    (net (code "75") (name "PB1{slash}ADC1_IN9_PRSR") (class "Default")
      (node (ref "C1") (pin "1") (pinfunction "1_1") (pintype "passive"))
      (node (ref "R8") (pin "2") (pinfunction "2_2") (pintype "passive"))
      (node (ref "U100") (pin "27") (pinfunction "PB1_27") (pintype "bidirectional"))
    )
    (net (code "76") (name "PB2{slash}BOOT1") (class "Default")
      (node (ref "JPROG") (pin "7") (pinfunction "7_7") (pintype "passive"))
      (node (ref "R103") (pin "1") (pinfunction "1_1") (pintype "passive"))
      (node (ref "U100") (pin "28") (pinfunction "PB2_28") (pintype "bidirectional"))
    )
    (net (code "77") (name "PB6{slash}I2C1_SCL") (class "Default")
      (node (ref "U100") (pin "58") (pinfunction "PB6_58") (pintype "bidirectional"))
    )
    (net (code "78") (name "PB7{slash}I2C1_SDA") (class "Default")
      (node (ref "U100") (pin "59") (pinfunction "PB7_59") (pintype "bidirectional"))
    )
    (net (code "79") (name "PB12{slash}CAN2_RX") (class "Default")
      (node (ref "DRX") (pin "C") (pinfunction "C_C") (pintype "passive"))
      (node (ref "U100") (pin "33") (pinfunction "PB12_33") (pintype "bidirectional"))
      (node (ref "U200") (pin "4") (pinfunction "RXD_4") (pintype "bidirectional"))
    )
    (net (code "80") (name "PB13{slash}CAN2_TX") (class "Default")
      (node (ref "DTX") (pin "C") (pinfunction "C_C") (pintype "passive"))
      (node (ref "U100") (pin "34") (pinfunction "PB13_34") (pintype "bidirectional"))
      (node (ref "U200") (pin "1") (pinfunction "TXD_1") (pintype "bidirectional"))
    )
    (net (code "81") (name "PC0{slash}SSI_MCLKB") (class "Default")
      (node (ref "U100") (pin "8") (pinfunction "PC0_8") (pintype "bidirectional"))
      (node (ref "U400") (pin "P6") (pinfunction "P6_MCLK_P6") (pintype "input"))
    )
    (net (code "82") (name "PC1{slash}ADC1_IN11_TEMP2") (class "Default")
      (node (ref "C801") (pin "1") (pinfunction "1_1") (pintype "passive"))
      (node (ref "R802") (pin "2") (pinfunction "2_2") (pintype "passive"))
      (node (ref "U100") (pin "9") (pinfunction "PC1_9") (pintype "bidirectional"))
    )
    (net (code "83") (name "PC2{slash}SSI_MDIN") (class "Default")
      (node (ref "U100") (pin "10") (pinfunction "PC2_10") (pintype "bidirectional"))
      (node (ref "U400") (pin "P8") (pinfunction "P8_DOUT_P8") (pintype "output"))
    )
    (net (code "84") (name "PC3{slash}SSI_MDOUT") (class "Default")
      (node (ref "U100") (pin "11") (pinfunction "PC3_11") (pintype "bidirectional"))
      (node (ref "U400") (pin "P7") (pinfunction "P7_DIN_P7") (pintype "input"))
    )
    (net (code "85") (name "PC4{slash}CAN_EN") (class "Default")
      (node (ref "R204") (pin "2") (pinfunction "2_2") (pintype "passive"))
      (node (ref "U100") (pin "24") (pinfunction "PC4_24") (pintype "bidirectional"))
      (node (ref "U200") (pin "8") (pinfunction "STB_8") (pintype "bidirectional"))
    )
    (net (code "86") (name "PC5{slash}SOLENOID_EN") (class "Default")
      (node (ref "QN901") (pin "G") (pinfunction "G_G") (pintype "bidirectional"))
      (node (ref "R902") (pin "2") (pinfunction "2_2") (pintype "passive"))
      (node (ref "U100") (pin "25") (pinfunction "PC5_25") (pintype "bidirectional"))
    )
    (net (code "87") (name "PC7{slash}SSI_SCK") (class "Default")
      (node (ref "U100") (pin "38") (pinfunction "PC7_38") (pintype "bidirectional"))
      (node (ref "U400") (pin "P1") (pinfunction "P1_SCLK_P1") (pintype "input"))
    )
    (net (code "88") (name "PRESSURE") (class "Default")
      (node (ref "JD04") (pin "1") (pinfunction "1_1") (pintype "passive"))
      (node (ref "JDPH") (pin "2") (pinfunction "2_2") (pintype "passive"))
      (node (ref "R2") (pin "1") (pinfunction "1_1") (pintype "passive"))
      (node (ref "TVS3") (pin "3") (pinfunction "C1A2_3") (pintype "passive"))
    )
    (net (code "89") (name "RST") (class "Default")
      (node (ref "JPROG") (pin "9") (pinfunction "9_9") (pintype "passive"))
    )
    (net (code "90") (name "SCK") (class "Default")
      (node (ref "JD04") (pin "9") (pinfunction "9_9") (pintype "passive"))
      (node (ref "R305") (pin "2") (pinfunction "2_2") (pintype "passive"))
    )
    (net (code "91") (name "SHIELD") (class "Default")
      (node (ref "C2") (pin "1") (pinfunction "1_1") (pintype "passive"))
      (node (ref "JD04") (pin "3") (pinfunction "3_3") (pintype "passive"))
      (node (ref "R1") (pin "1") (pinfunction "1_1") (pintype "passive"))
    )
    (net (code "92") (name "V_USB") (class "Default")
      (node (ref "D1") (pin "2") (pinfunction "A_2") (pintype "passive"))
      (node (ref "F3") (pin "P2") (pinfunction "P$2_P2") (pintype "power_in"))
    )
    (net (code "93") (name "unconnected-(R610-Pad1)") (class "Default")
      (node (ref "R610") (pin "1") (pinfunction "1_1") (pintype "passive"))
    )
    (net (code "94") (name "unconnected-(U100A-PA0-WKUP-Pad14)") (class "Default")
      (node (ref "U100") (pin "14") (pinfunction "PA0-WKUP_14") (pintype "bidirectional"))
    )
    (net (code "95") (name "unconnected-(U100A-PA1-Pad15)") (class "Default")
      (node (ref "U100") (pin "15") (pinfunction "PA1_15") (pintype "bidirectional"))
    )
    (net (code "96") (name "unconnected-(U100A-PA2-Pad16)") (class "Default")
      (node (ref "U100") (pin "16") (pinfunction "PA2_16") (pintype "bidirectional"))
    )
    (net (code "97") (name "unconnected-(U100A-PA8-Pad41)") (class "Default")
      (node (ref "U100") (pin "41") (pinfunction "PA8_41") (pintype "bidirectional"))
    )
    (net (code "98") (name "unconnected-(U100A-PA13-Pad46)") (class "Default")
      (node (ref "U100") (pin "46") (pinfunction "PA13_46") (pintype "bidirectional"))
    )
    (net (code "99") (name "unconnected-(U100A-PA14-Pad49)") (class "Default")
      (node (ref "U100") (pin "49") (pinfunction "PA14_49") (pintype "bidirectional"))
    )
    (net (code "100") (name "unconnected-(U100A-PA15-Pad50)") (class "Default")
      (node (ref "U100") (pin "50") (pinfunction "PA15_50") (pintype "bidirectional"))
    )
    (net (code "101") (name "unconnected-(U100A-PB0-Pad26)") (class "Default")
      (node (ref "U100") (pin "26") (pinfunction "PB0_26") (pintype "bidirectional"))
    )
    (net (code "102") (name "unconnected-(U100A-PB3-Pad55)") (class "Default")
      (node (ref "U100") (pin "55") (pinfunction "PB3_55") (pintype "bidirectional"))
    )
    (net (code "103") (name "unconnected-(U100A-PB4-Pad56)") (class "Default")
      (node (ref "U100") (pin "56") (pinfunction "PB4_56") (pintype "bidirectional"))
    )
    (net (code "104") (name "unconnected-(U100A-PB5-Pad57)") (class "Default")
      (node (ref "U100") (pin "57") (pinfunction "PB5_57") (pintype "bidirectional"))
    )
    (net (code "105") (name "unconnected-(U100A-PB8-Pad61)") (class "Default")
      (node (ref "U100") (pin "61") (pinfunction "PB8_61") (pintype "bidirectional"))
    )
    (net (code "106") (name "unconnected-(U100A-PB9-Pad62)") (class "Default")
      (node (ref "U100") (pin "62") (pinfunction "PB9_62") (pintype "bidirectional"))
    )
    (net (code "107") (name "unconnected-(U100A-PB10-Pad29)") (class "Default")
      (node (ref "U100") (pin "29") (pinfunction "PB10_29") (pintype "bidirectional"))
    )
    (net (code "108") (name "unconnected-(U100A-PB14-Pad35)") (class "Default")
      (node (ref "U100") (pin "35") (pinfunction "PB14_35") (pintype "bidirectional"))
    )
    (net (code "109") (name "unconnected-(U100A-PB15-Pad36)") (class "Default")
      (node (ref "U100") (pin "36") (pinfunction "PB15_36") (pintype "bidirectional"))
    )
    (net (code "110") (name "unconnected-(U100A-PC6-Pad37)") (class "Default")
      (node (ref "U100") (pin "37") (pinfunction "PC6_37") (pintype "bidirectional"))
    )
    (net (code "111") (name "unconnected-(U100A-PC8-Pad39)") (class "Default")
      (node (ref "U100") (pin "39") (pinfunction "PC8_39") (pintype "bidirectional"))
    )
    (net (code "112") (name "unconnected-(U100A-PC9-Pad40)") (class "Default")
      (node (ref "U100") (pin "40") (pinfunction "PC9_40") (pintype "bidirectional"))
    )
    (net (code "113") (name "unconnected-(U100A-PC10-Pad51)") (class "Default")
      (node (ref "U100") (pin "51") (pinfunction "PC10_51") (pintype "bidirectional"))
    )
    (net (code "114") (name "unconnected-(U100A-PC11-Pad52)") (class "Default")
      (node (ref "U100") (pin "52") (pinfunction "PC11_52") (pintype "bidirectional"))
    )
    (net (code "115") (name "unconnected-(U100A-PC12-Pad53)") (class "Default")
      (node (ref "U100") (pin "53") (pinfunction "PC12_53") (pintype "bidirectional"))
    )
    (net (code "116") (name "unconnected-(U100A-PC13-Pad2)") (class "Default")
      (node (ref "U100") (pin "2") (pinfunction "PC13_2") (pintype "bidirectional"))
    )
    (net (code "117") (name "unconnected-(U100A-PC14-Pad3)") (class "Default")
      (node (ref "U100") (pin "3") (pinfunction "PC14_3") (pintype "bidirectional"))
    )
    (net (code "118") (name "unconnected-(U100A-PC15-Pad4)") (class "Default")
      (node (ref "U100") (pin "4") (pinfunction "PC15_4") (pintype "bidirectional"))
    )
    (net (code "119") (name "unconnected-(U100A-PD2-Pad54)") (class "Default")
      (node (ref "U100") (pin "54") (pinfunction "PD2_54") (pintype "bidirectional"))
    )
    (net (code "120") (name "unconnected-(U400-P3_PV-PadP3)") (class "Default")
      (node (ref "U400") (pin "P3") (pinfunction "P3_PV_P3") (pintype "no_connect"))
    )
    (net (code "121") (name "unconnected-(U400-P4_PEN-PadP4)") (class "Default")
      (node (ref "U400") (pin "P4") (pinfunction "P4_PEN_P4") (pintype "no_connect"))
    )
    (net (code "122") (name "unconnected-(U500-AUX_CL-Pad7)") (class "Default")
      (node (ref "U500") (pin "7") (pinfunction "AUX_CL_7") (pintype "bidirectional"))
    )
    (net (code "123") (name "unconnected-(U500-AUX_DA-Pad21)") (class "Default")
      (node (ref "U500") (pin "21") (pinfunction "AUX_DA_21") (pintype "bidirectional"))
    )
    (net (code "124") (name "unconnected-(U500-FSYNC-Pad11)") (class "Default")
      (node (ref "U500") (pin "11") (pinfunction "FSYNC_11") (pintype "bidirectional"))
    )
  )
)
